# ddk-final-1.net
KiCad netlist of a schematic drawn in EAGLE
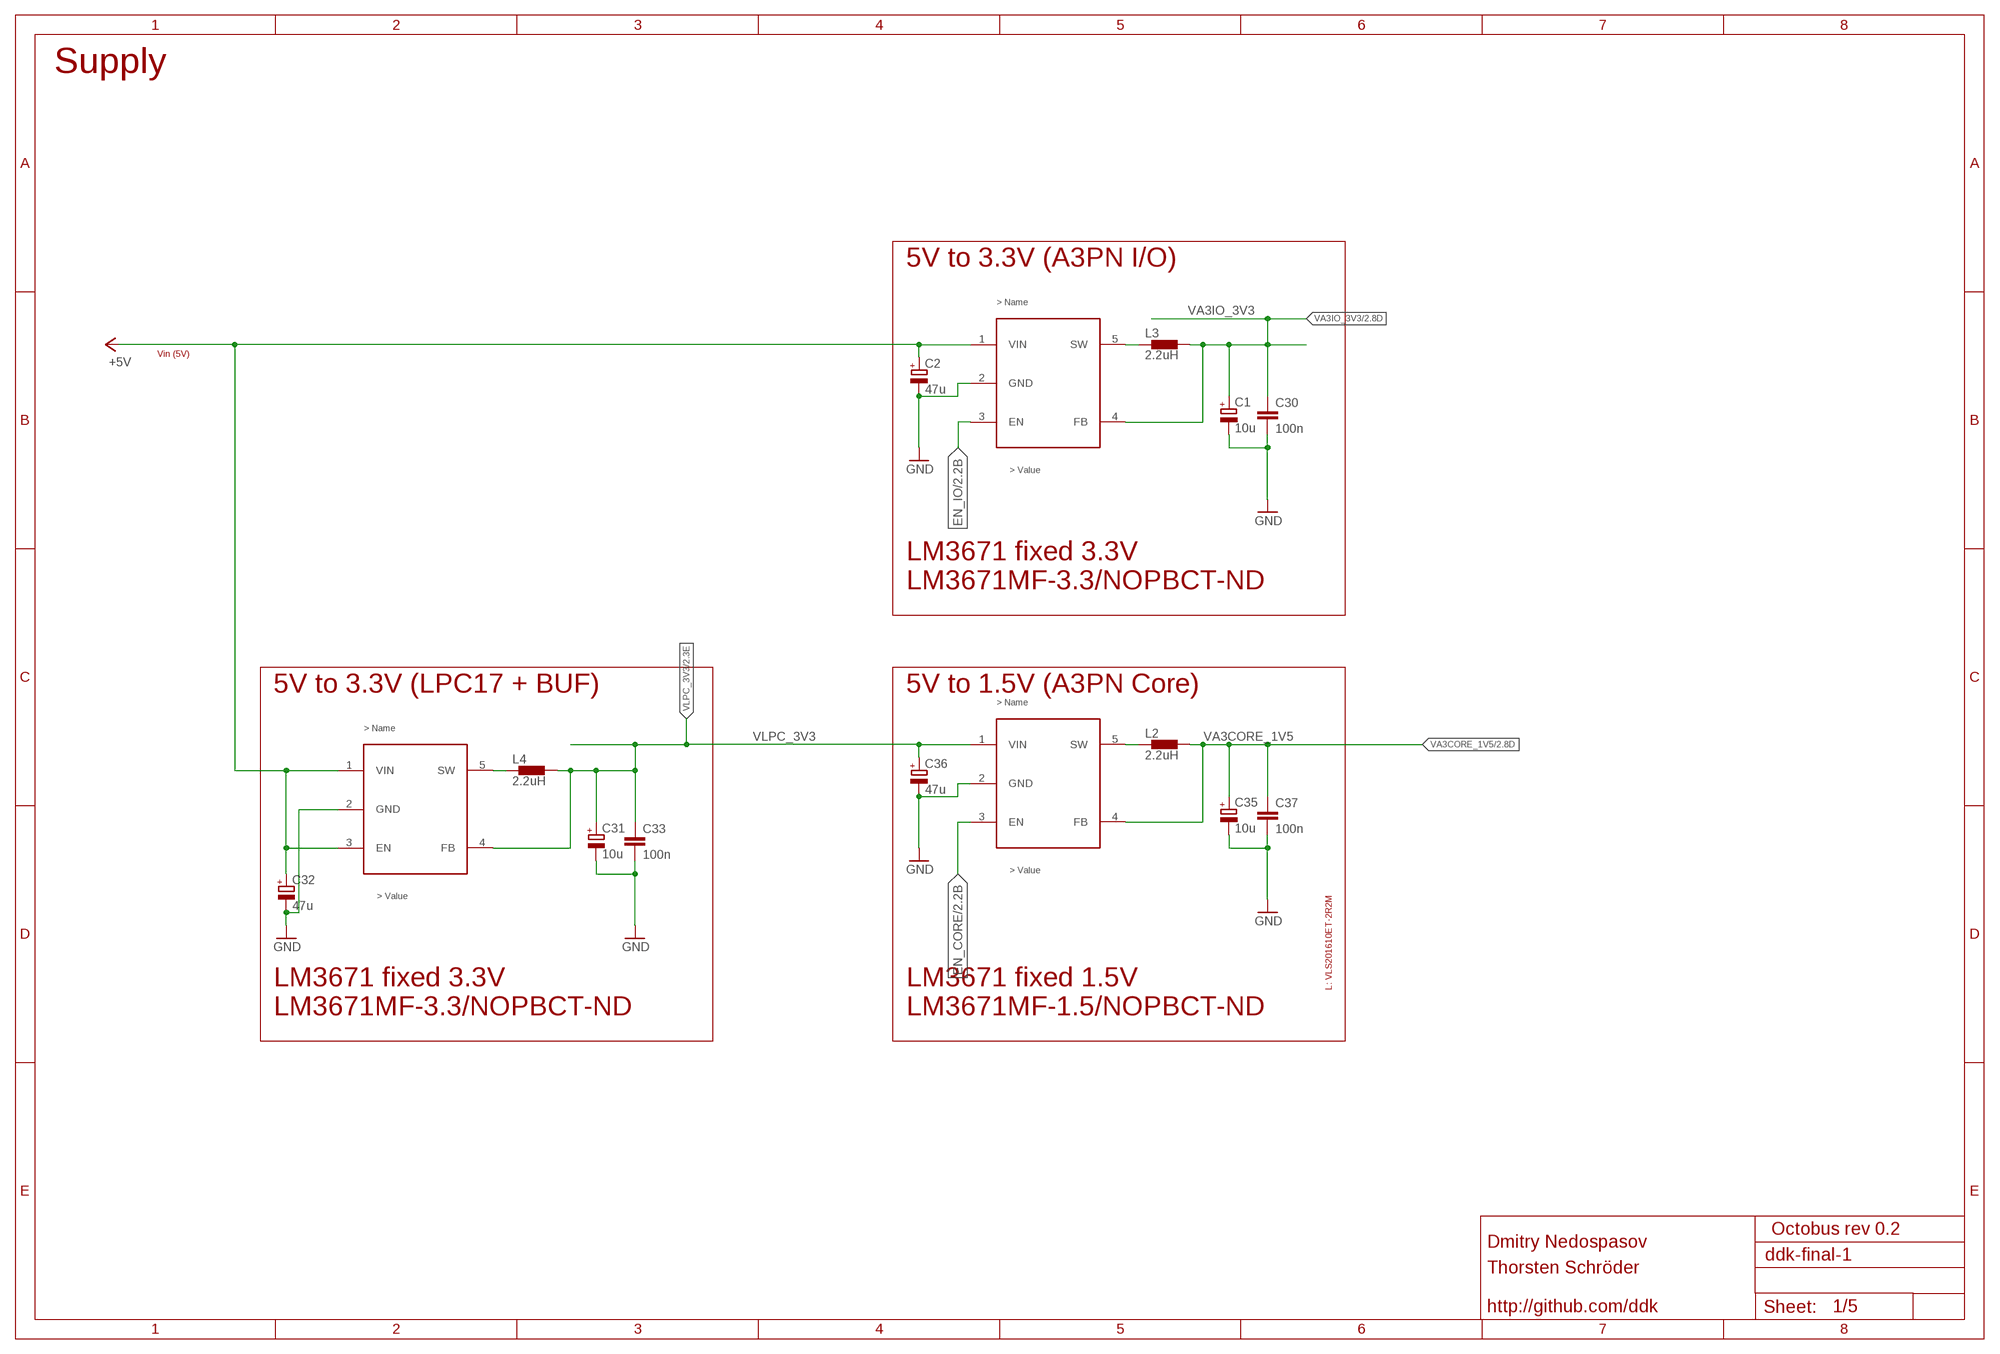
[diagram p0: schematic, sheet 1]
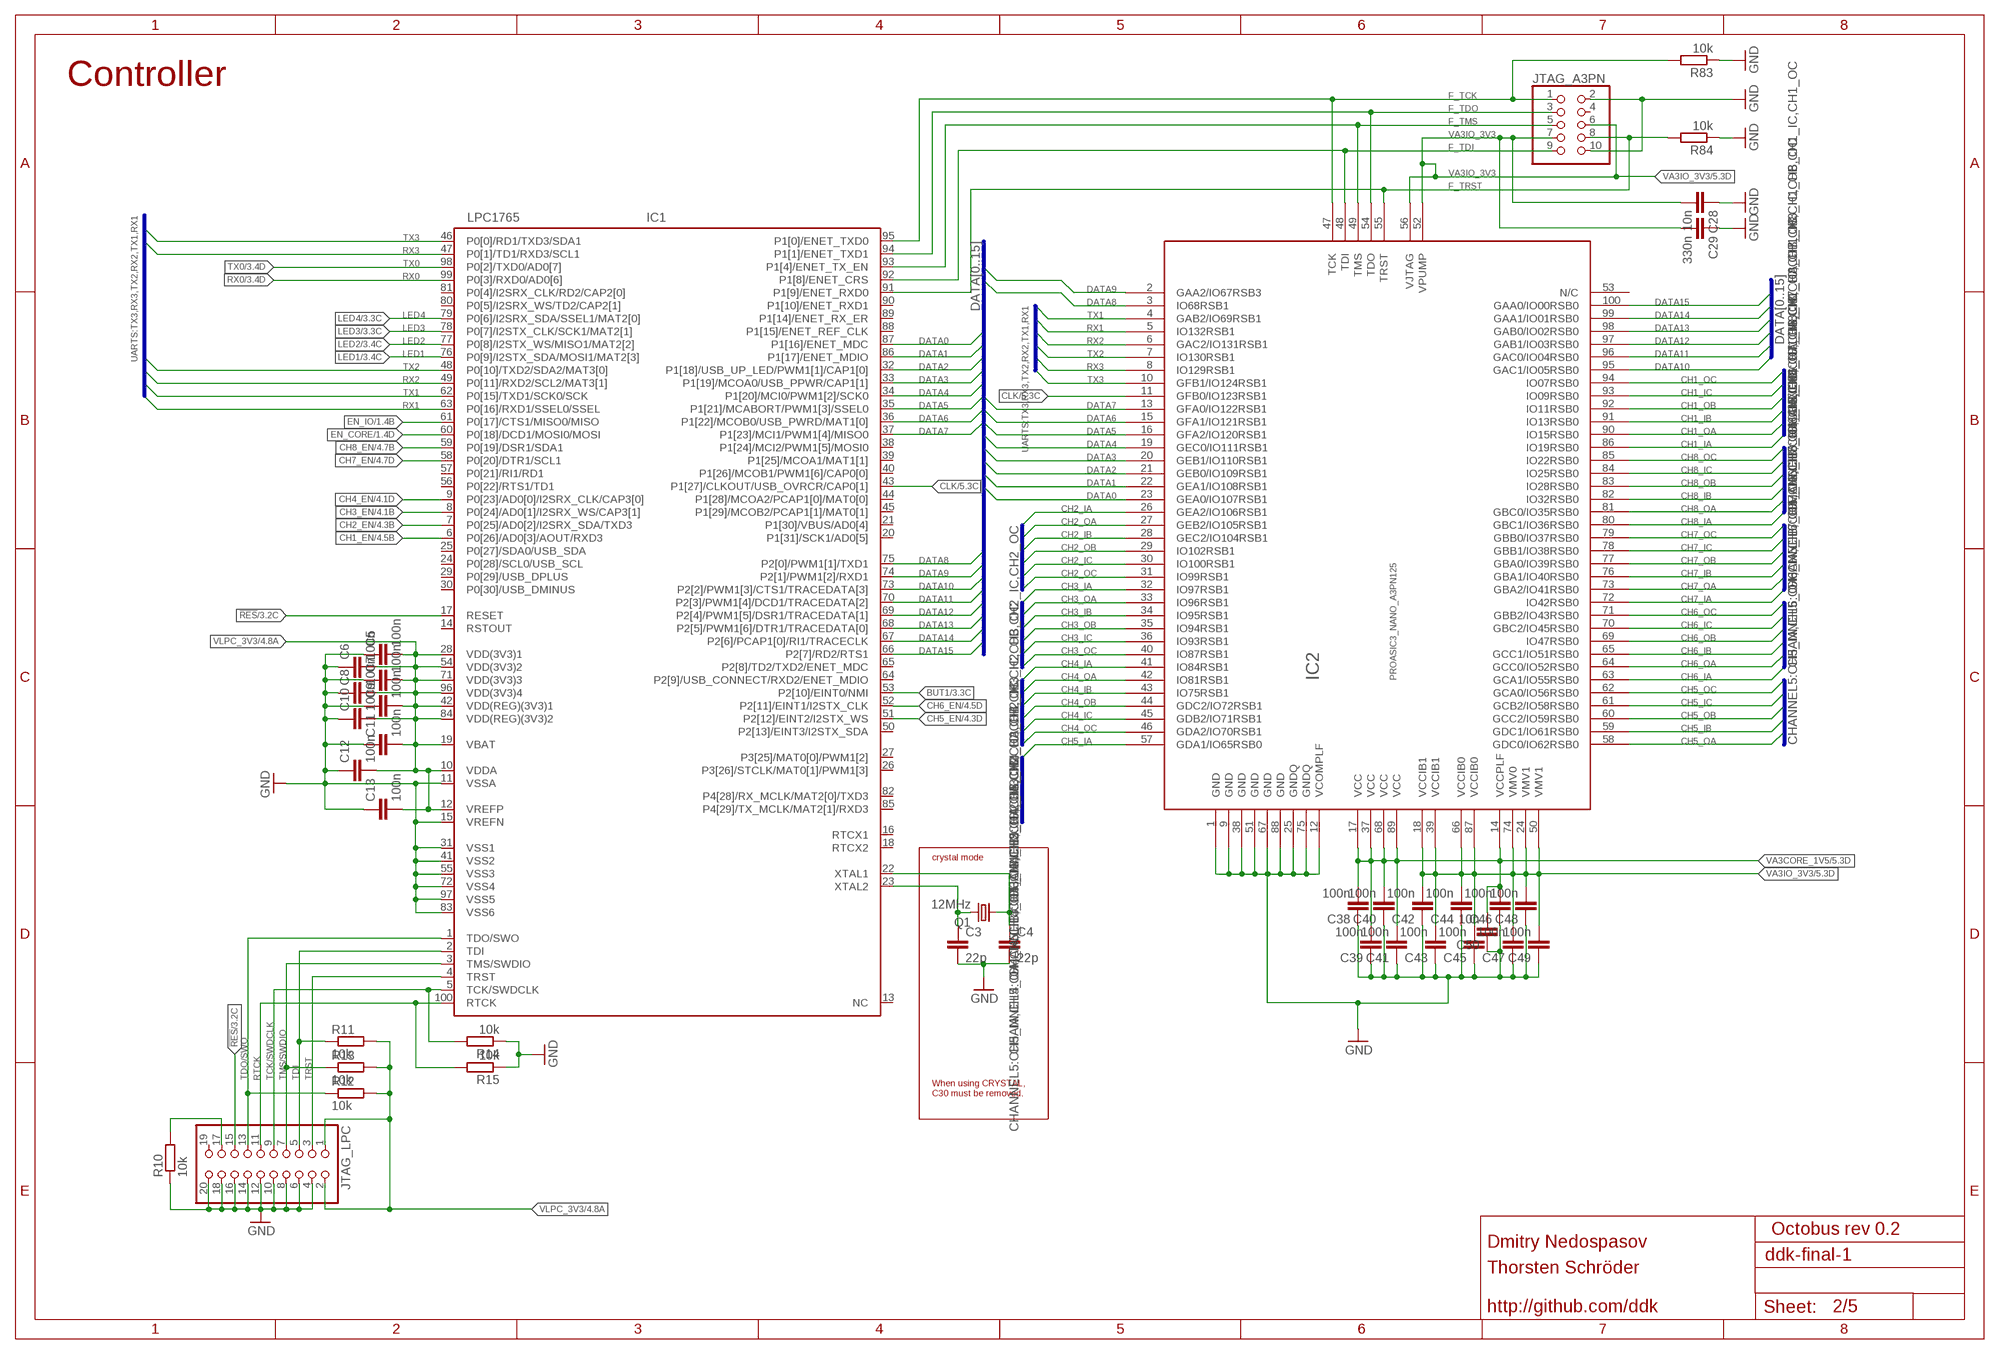
[diagram p1: schematic, sheet 2]
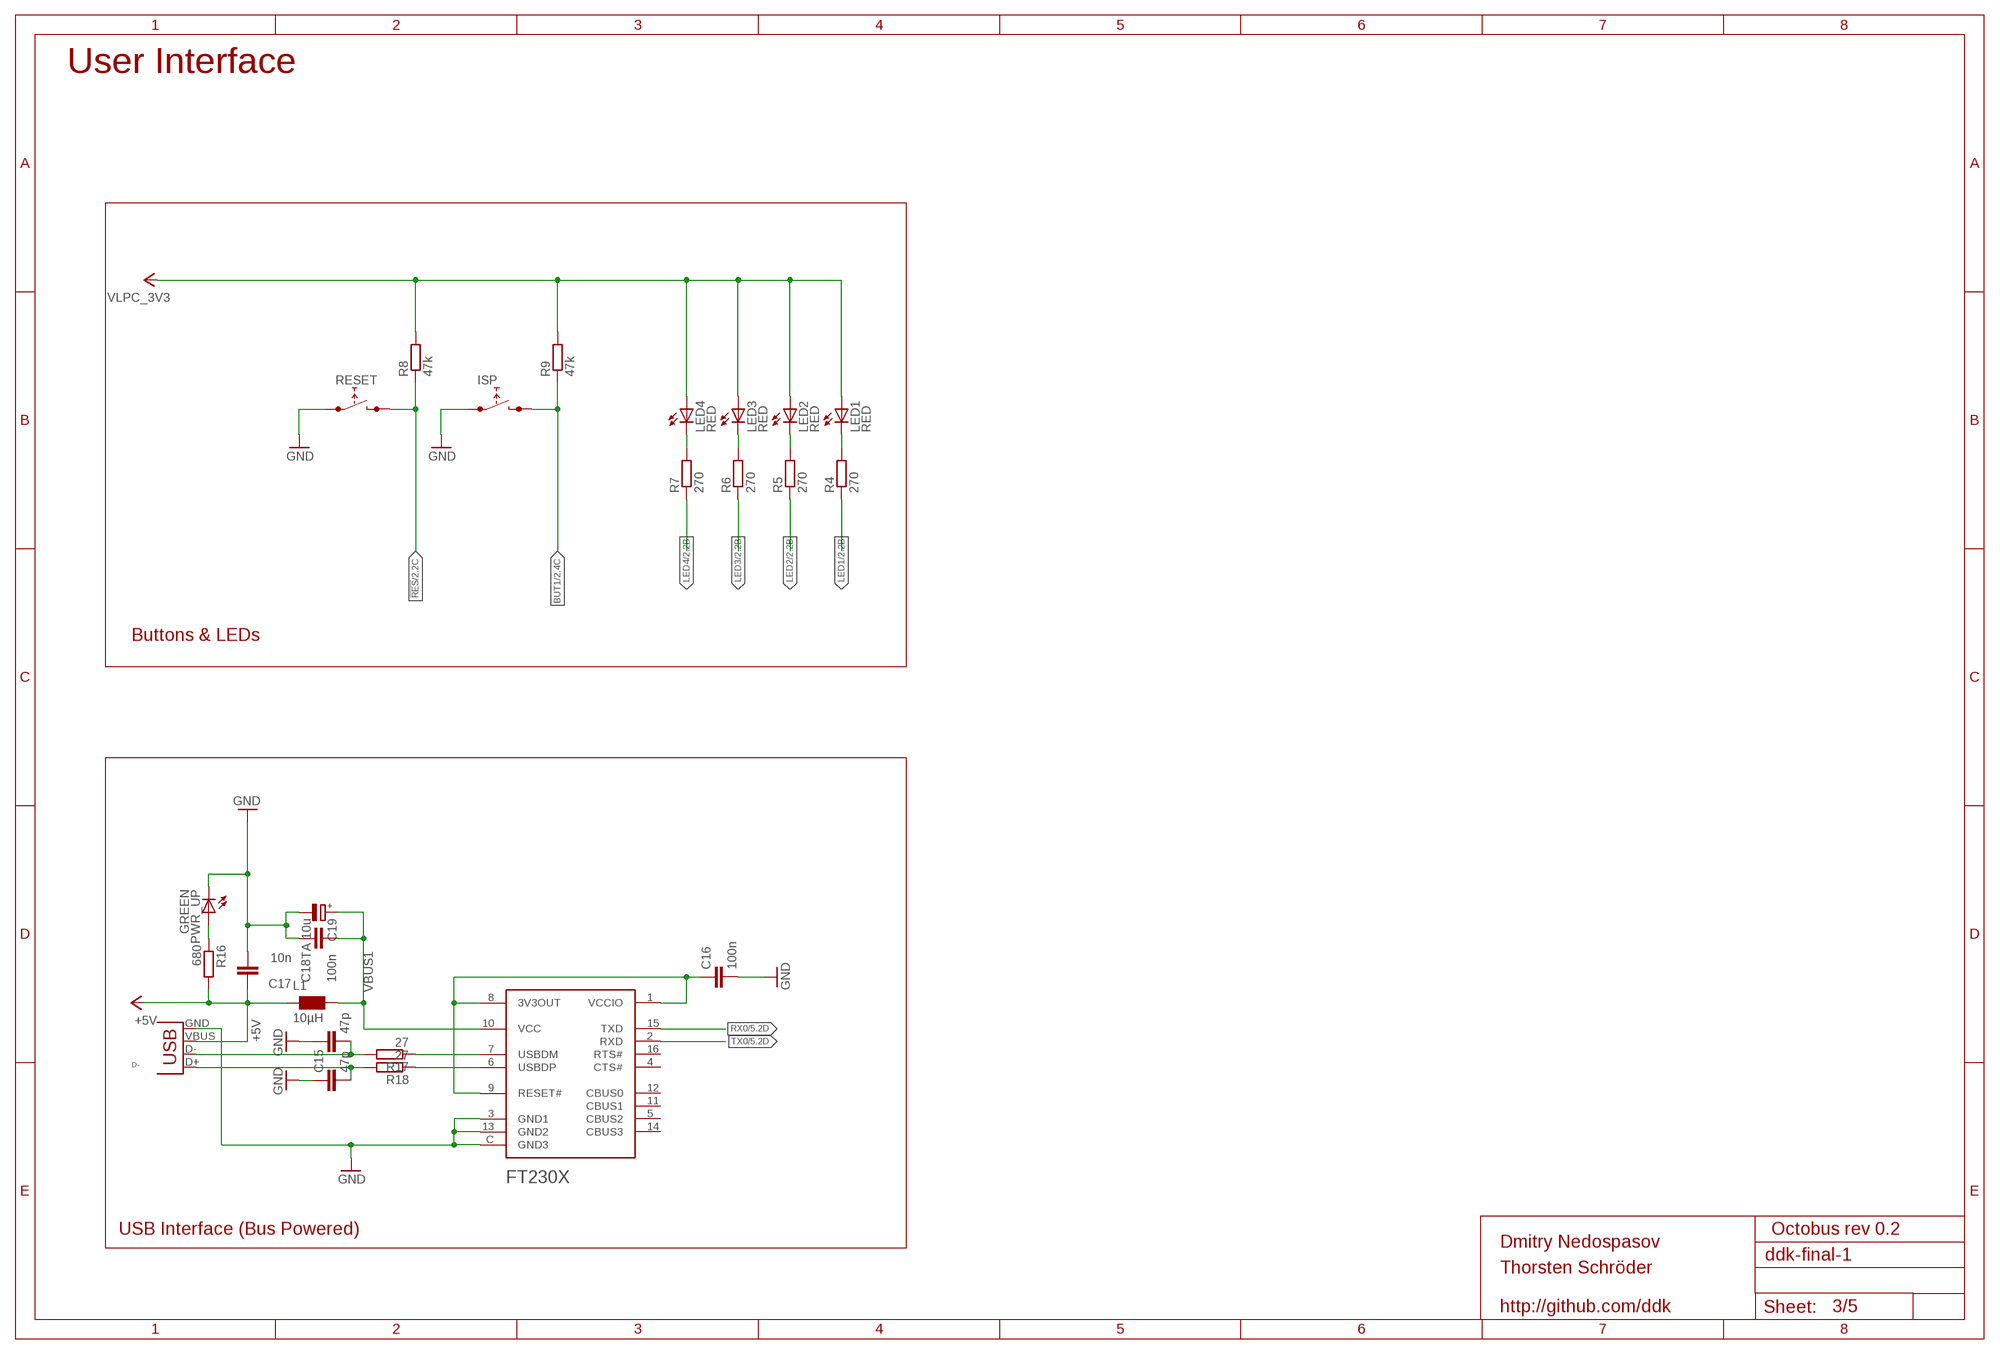
[diagram p2: schematic, sheet 3]
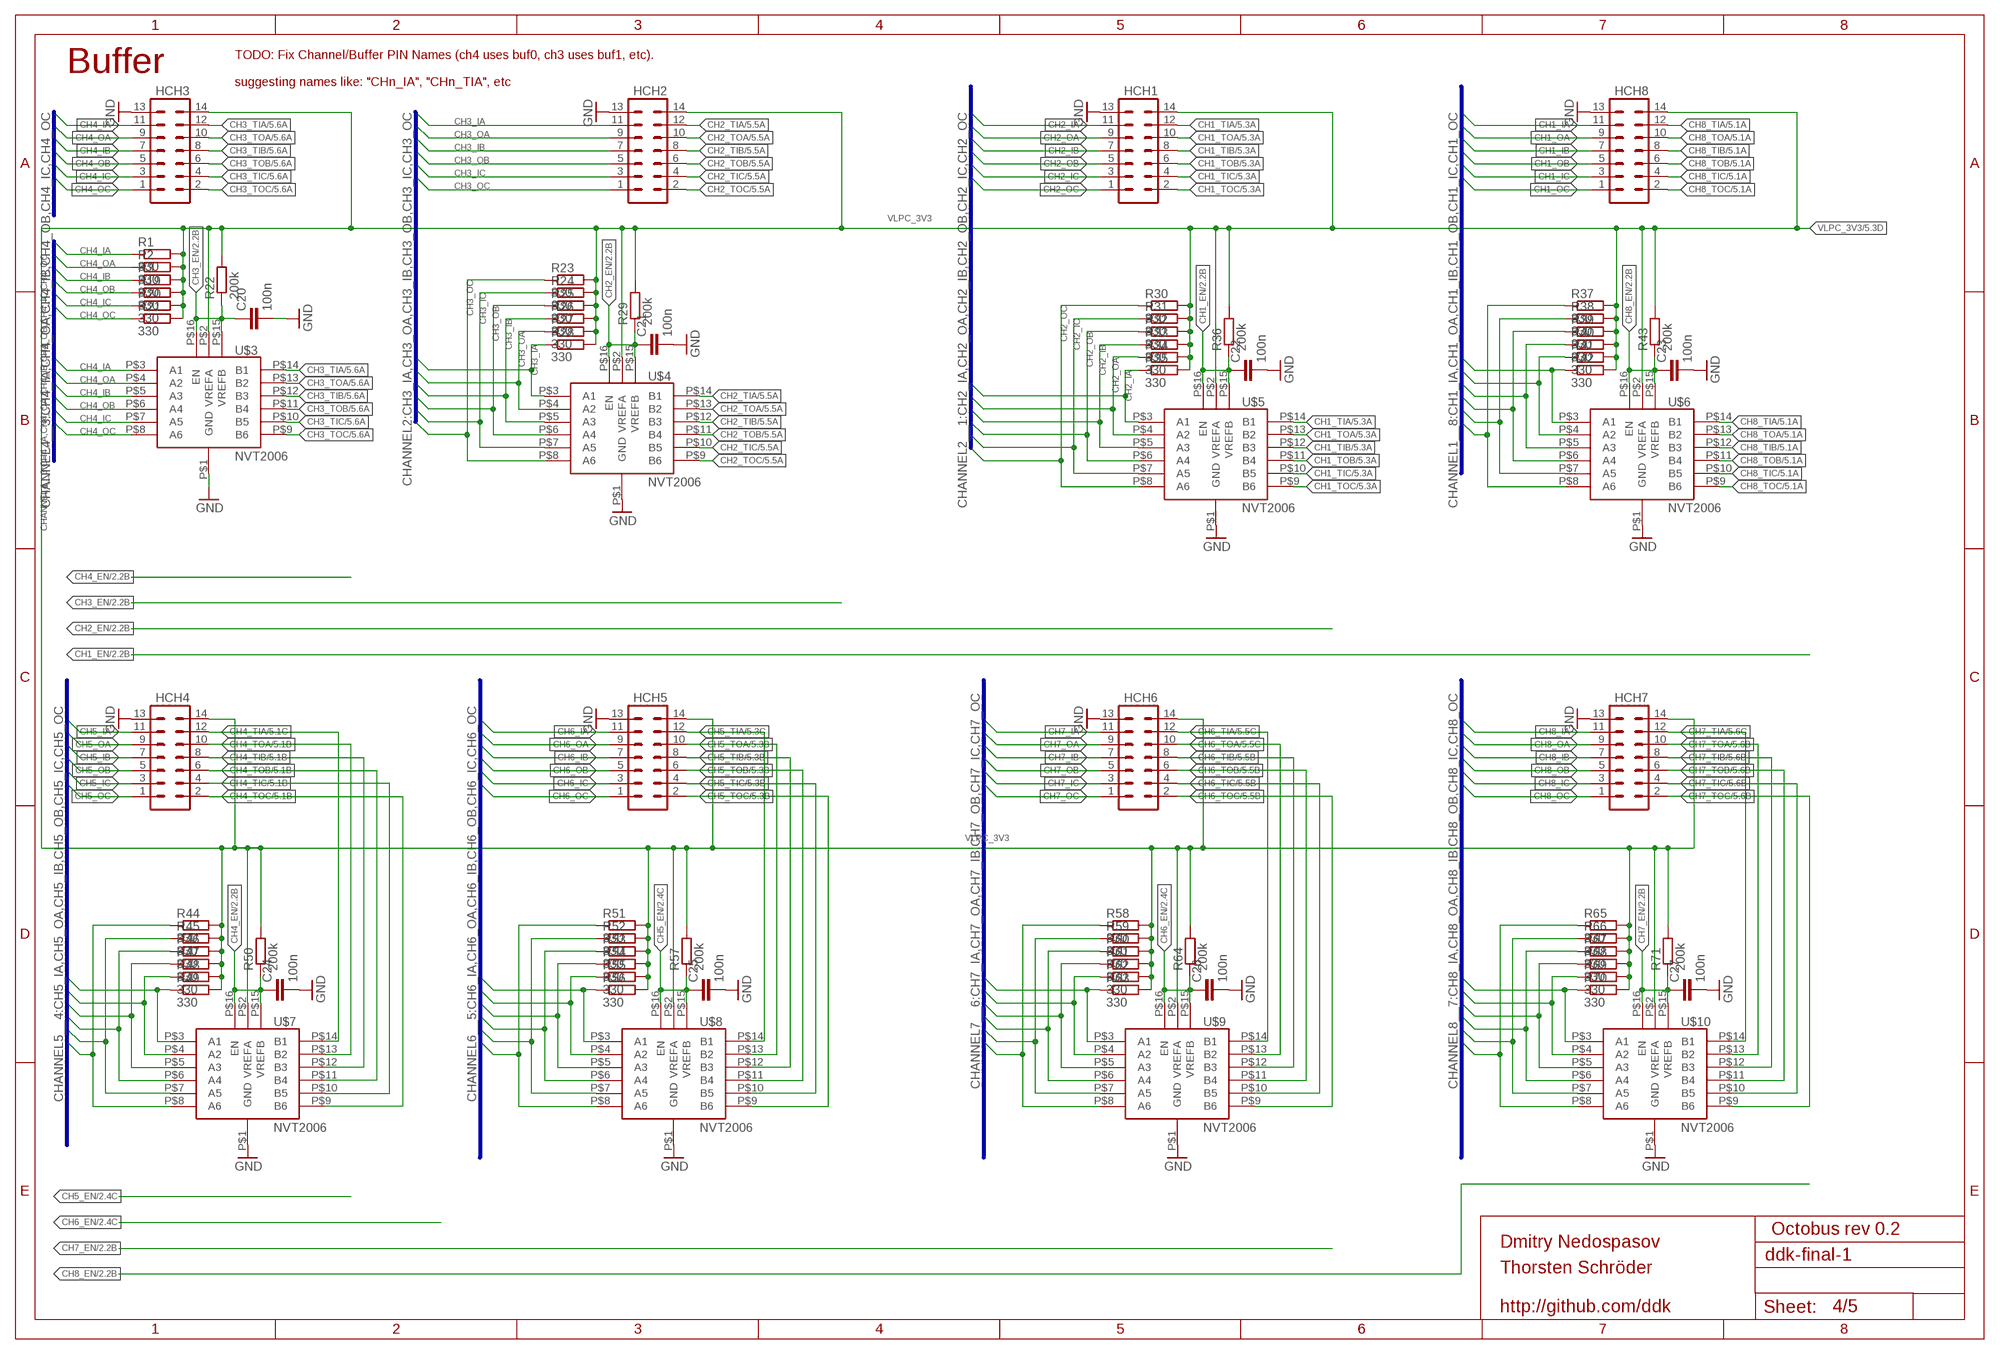
[diagram p3: schematic, sheet 4]
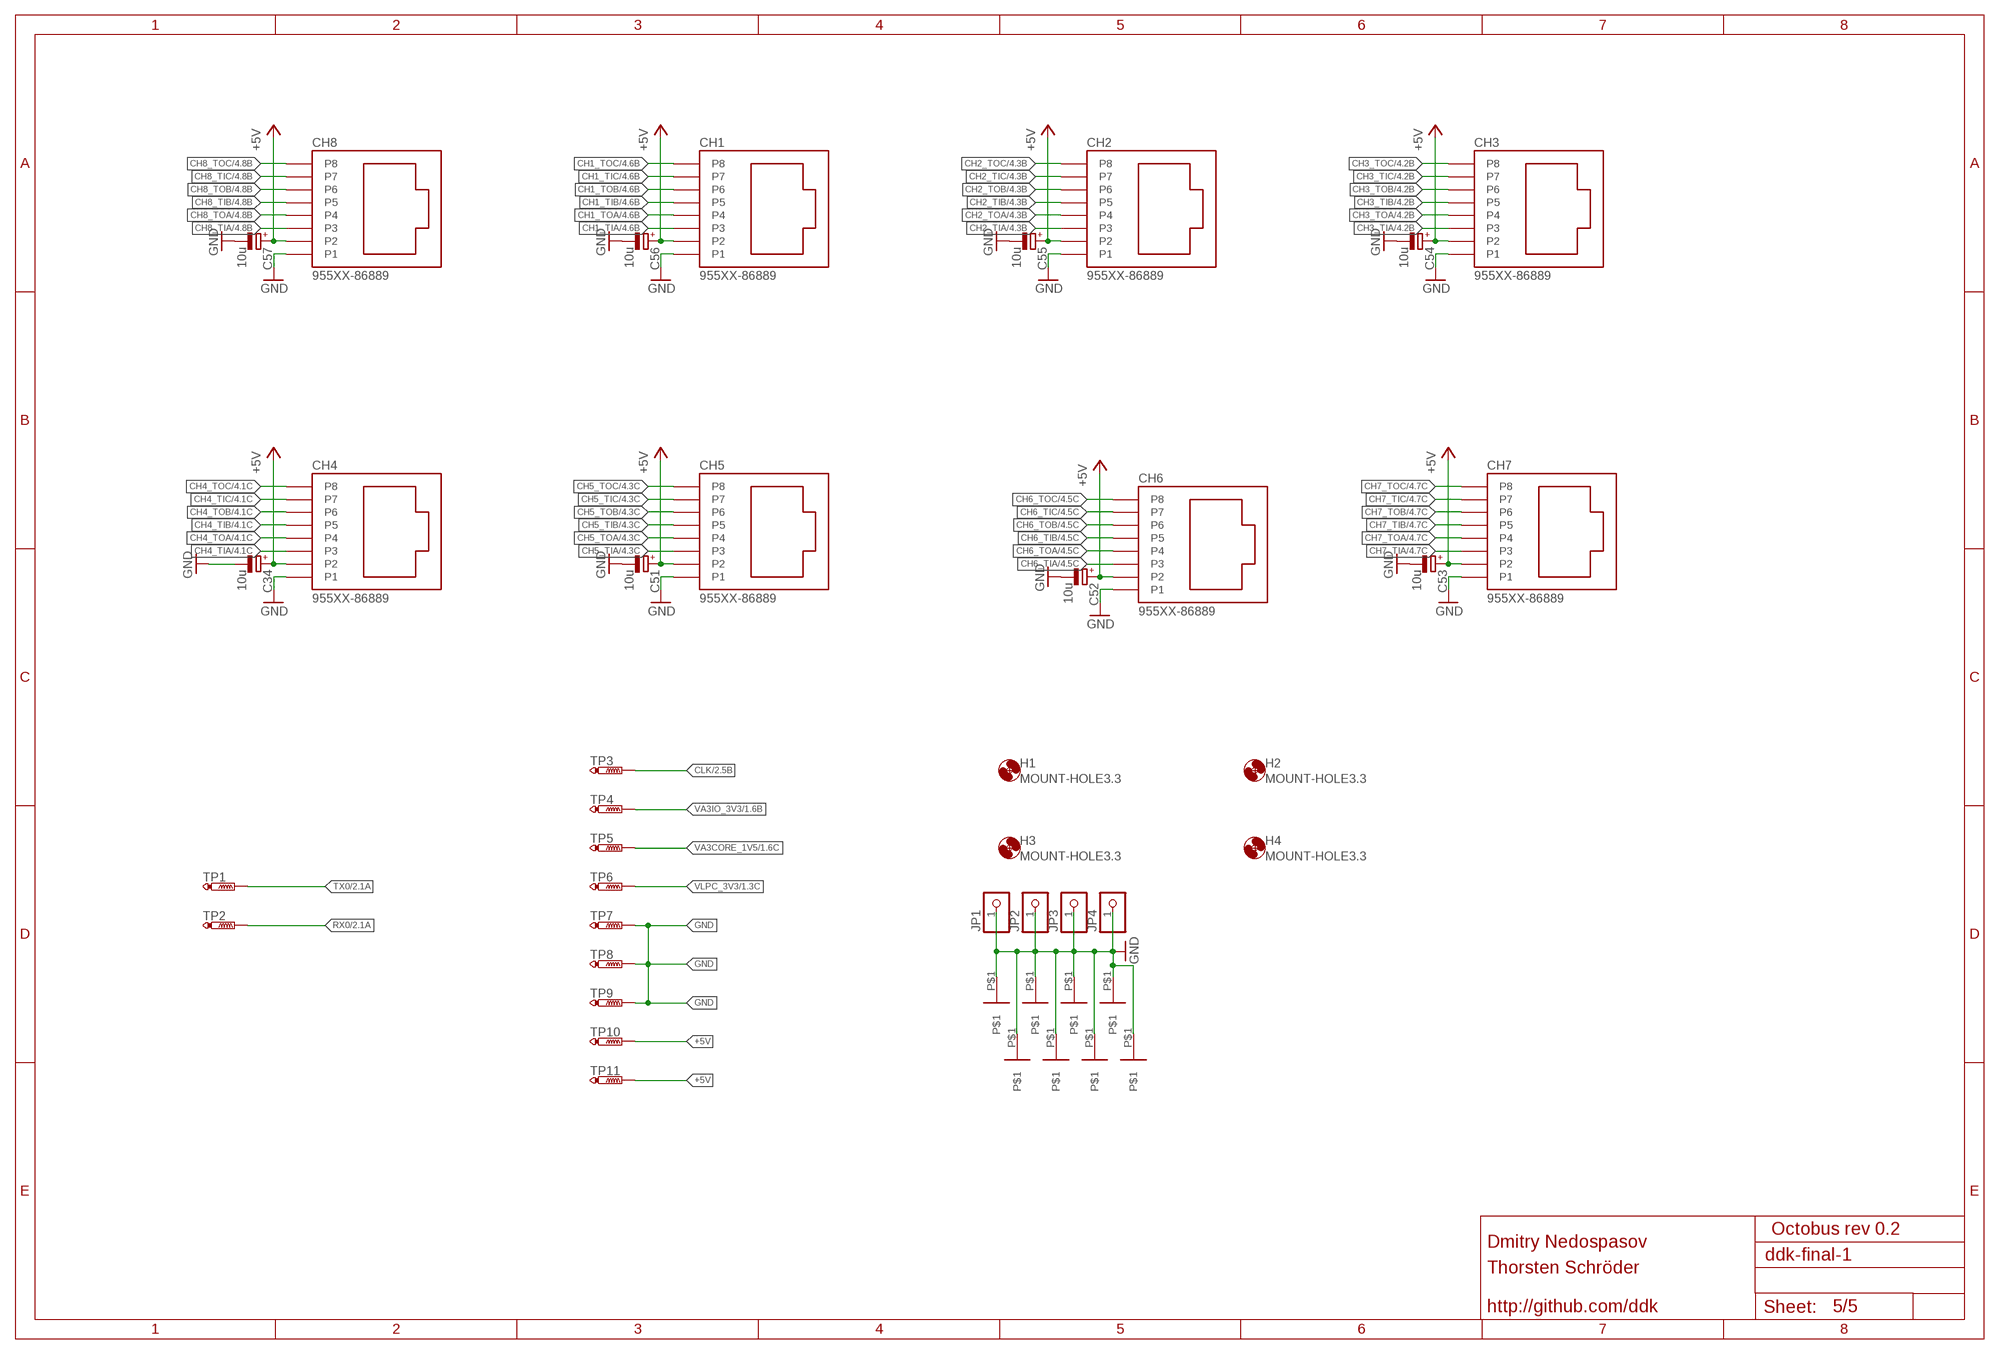
[diagram p4: schematic, sheet 5]

(export (version "E")
  (design (tool "Eeschema 10.0.6"))
  (components
    (comp (ref "C20")
      (value "100n")
      (footprint "eagle-import:C0603")
      (libsource (lib "eagle-import") (part "C-EUC0603"))
    )
    (comp (ref "C21")
      (value "100n")
      (footprint "eagle-import:C0603")
      (libsource (lib "eagle-import") (part "C-EUC0603"))
    )
    (comp (ref "C22")
      (value "100n")
      (footprint "eagle-import:C0603")
      (libsource (lib "eagle-import") (part "C-EUC0603"))
    )
    (comp (ref "C23")
      (value "100n")
      (footprint "eagle-import:C0603")
      (libsource (lib "eagle-import") (part "C-EUC0603"))
    )
    (comp (ref "C24")
      (value "100n")
      (footprint "eagle-import:C0603")
      (libsource (lib "eagle-import") (part "C-EUC0603"))
    )
    (comp (ref "C25")
      (value "100n")
      (footprint "eagle-import:C0603")
      (libsource (lib "eagle-import") (part "C-EUC0603"))
    )
    (comp (ref "C26")
      (value "100n")
      (footprint "eagle-import:C0603")
      (libsource (lib "eagle-import") (part "C-EUC0603"))
    )
    (comp (ref "C27")
      (value "100n")
      (footprint "eagle-import:C0603")
      (libsource (lib "eagle-import") (part "C-EUC0603"))
    )
    (comp (ref "HCH1")
      (value "MA07-2")
      (footprint "eagle-import:MA07-2")
      (libsource (lib "eagle-import") (part "MA07-2"))
    )
    (comp (ref "HCH2")
      (value "MA07-2")
      (footprint "eagle-import:MA07-2")
      (libsource (lib "eagle-import") (part "MA07-2"))
    )
    (comp (ref "HCH3")
      (value "MA07-2")
      (footprint "eagle-import:MA07-2")
      (libsource (lib "eagle-import") (part "MA07-2"))
    )
    (comp (ref "HCH4")
      (value "MA07-2")
      (footprint "eagle-import:MA07-2")
      (libsource (lib "eagle-import") (part "MA07-2"))
    )
    (comp (ref "HCH5")
      (value "MA07-2")
      (footprint "eagle-import:MA07-2")
      (libsource (lib "eagle-import") (part "MA07-2"))
    )
    (comp (ref "HCH6")
      (value "MA07-2")
      (footprint "eagle-import:MA07-2")
      (libsource (lib "eagle-import") (part "MA07-2"))
    )
    (comp (ref "HCH7")
      (value "MA07-2")
      (footprint "eagle-import:MA07-2")
      (libsource (lib "eagle-import") (part "MA07-2"))
    )
    (comp (ref "HCH8")
      (value "MA07-2")
      (footprint "eagle-import:MA07-2")
      (libsource (lib "eagle-import") (part "MA07-2"))
    )
    (comp (ref "R1")
      (value "330")
      (footprint "eagle-import:R0603")
      (libsource (lib "eagle-import") (part "R-EU_R0603"))
    )
    (comp (ref "R2")
      (value "330")
      (footprint "eagle-import:R0603")
      (libsource (lib "eagle-import") (part "R-EU_R0603"))
    )
    (comp (ref "R3")
      (value "330")
      (footprint "eagle-import:R0603")
      (libsource (lib "eagle-import") (part "R-EU_R0603"))
    )
    (comp (ref "R19")
      (value "330")
      (footprint "eagle-import:R0603")
      (libsource (lib "eagle-import") (part "R-EU_R0603"))
    )
    (comp (ref "R20")
      (value "330")
      (footprint "eagle-import:R0603")
      (libsource (lib "eagle-import") (part "R-EU_R0603"))
    )
    (comp (ref "R21")
      (value "330")
      (footprint "eagle-import:R0603")
      (libsource (lib "eagle-import") (part "R-EU_R0603"))
    )
    (comp (ref "R22")
      (value "200k")
      (footprint "eagle-import:R0603")
      (libsource (lib "eagle-import") (part "R-EU_R0603"))
    )
    (comp (ref "R23")
      (value "330")
      (footprint "eagle-import:R0603")
      (libsource (lib "eagle-import") (part "R-EU_R0603"))
    )
    (comp (ref "R24")
      (value "330")
      (footprint "eagle-import:R0603")
      (libsource (lib "eagle-import") (part "R-EU_R0603"))
    )
    (comp (ref "R25")
      (value "330")
      (footprint "eagle-import:R0603")
      (libsource (lib "eagle-import") (part "R-EU_R0603"))
    )
    (comp (ref "R26")
      (value "330")
      (footprint "eagle-import:R0603")
      (libsource (lib "eagle-import") (part "R-EU_R0603"))
    )
    (comp (ref "R27")
      (value "330")
      (footprint "eagle-import:R0603")
      (libsource (lib "eagle-import") (part "R-EU_R0603"))
    )
    (comp (ref "R28")
      (value "330")
      (footprint "eagle-import:R0603")
      (libsource (lib "eagle-import") (part "R-EU_R0603"))
    )
    (comp (ref "R29")
      (value "200k")
      (footprint "eagle-import:R0603")
      (libsource (lib "eagle-import") (part "R-EU_R0603"))
    )
    (comp (ref "R30")
      (value "330")
      (footprint "eagle-import:R0603")
      (libsource (lib "eagle-import") (part "R-EU_R0603"))
    )
    (comp (ref "R31")
      (value "330")
      (footprint "eagle-import:R0603")
      (libsource (lib "eagle-import") (part "R-EU_R0603"))
    )
    (comp (ref "R32")
      (value "330")
      (footprint "eagle-import:R0603")
      (libsource (lib "eagle-import") (part "R-EU_R0603"))
    )
    (comp (ref "R33")
      (value "330")
      (footprint "eagle-import:R0603")
      (libsource (lib "eagle-import") (part "R-EU_R0603"))
    )
    (comp (ref "R34")
      (value "330")
      (footprint "eagle-import:R0603")
      (libsource (lib "eagle-import") (part "R-EU_R0603"))
    )
    (comp (ref "R35")
      (value "330")
      (footprint "eagle-import:R0603")
      (libsource (lib "eagle-import") (part "R-EU_R0603"))
    )
    (comp (ref "R36")
      (value "200k")
      (footprint "eagle-import:R0603")
      (libsource (lib "eagle-import") (part "R-EU_R0603"))
    )
    (comp (ref "R37")
      (value "330")
      (footprint "eagle-import:R0603")
      (libsource (lib "eagle-import") (part "R-EU_R0603"))
    )
    (comp (ref "R38")
      (value "330")
      (footprint "eagle-import:R0603")
      (libsource (lib "eagle-import") (part "R-EU_R0603"))
    )
    (comp (ref "R39")
      (value "330")
      (footprint "eagle-import:R0603")
      (libsource (lib "eagle-import") (part "R-EU_R0603"))
    )
    (comp (ref "R40")
      (value "330")
      (footprint "eagle-import:R0603")
      (libsource (lib "eagle-import") (part "R-EU_R0603"))
    )
    (comp (ref "R41")
      (value "330")
      (footprint "eagle-import:R0603")
      (libsource (lib "eagle-import") (part "R-EU_R0603"))
    )
    (comp (ref "R42")
      (value "330")
      (footprint "eagle-import:R0603")
      (libsource (lib "eagle-import") (part "R-EU_R0603"))
    )
    (comp (ref "R43")
      (value "200k")
      (footprint "eagle-import:R0603")
      (libsource (lib "eagle-import") (part "R-EU_R0603"))
    )
    (comp (ref "R44")
      (value "330")
      (footprint "eagle-import:R0603")
      (libsource (lib "eagle-import") (part "R-EU_R0603"))
    )
    (comp (ref "R45")
      (value "330")
      (footprint "eagle-import:R0603")
      (libsource (lib "eagle-import") (part "R-EU_R0603"))
    )
    (comp (ref "R46")
      (value "330")
      (footprint "eagle-import:R0603")
      (libsource (lib "eagle-import") (part "R-EU_R0603"))
    )
    (comp (ref "R47")
      (value "330")
      (footprint "eagle-import:R0603")
      (libsource (lib "eagle-import") (part "R-EU_R0603"))
    )
    (comp (ref "R48")
      (value "330")
      (footprint "eagle-import:R0603")
      (libsource (lib "eagle-import") (part "R-EU_R0603"))
    )
    (comp (ref "R49")
      (value "330")
      (footprint "eagle-import:R0603")
      (libsource (lib "eagle-import") (part "R-EU_R0603"))
    )
    (comp (ref "R50")
      (value "200k")
      (footprint "eagle-import:R0603")
      (libsource (lib "eagle-import") (part "R-EU_R0603"))
    )
    (comp (ref "R51")
      (value "330")
      (footprint "eagle-import:R0603")
      (libsource (lib "eagle-import") (part "R-EU_R0603"))
    )
    (comp (ref "R52")
      (value "330")
      (footprint "eagle-import:R0603")
      (libsource (lib "eagle-import") (part "R-EU_R0603"))
    )
    (comp (ref "R53")
      (value "330")
      (footprint "eagle-import:R0603")
      (libsource (lib "eagle-import") (part "R-EU_R0603"))
    )
    (comp (ref "R54")
      (value "330")
      (footprint "eagle-import:R0603")
      (libsource (lib "eagle-import") (part "R-EU_R0603"))
    )
    (comp (ref "R55")
      (value "330")
      (footprint "eagle-import:R0603")
      (libsource (lib "eagle-import") (part "R-EU_R0603"))
    )
    (comp (ref "R56")
      (value "330")
      (footprint "eagle-import:R0603")
      (libsource (lib "eagle-import") (part "R-EU_R0603"))
    )
    (comp (ref "R57")
      (value "200k")
      (footprint "eagle-import:R0603")
      (libsource (lib "eagle-import") (part "R-EU_R0603"))
    )
    (comp (ref "R58")
      (value "330")
      (footprint "eagle-import:R0603")
      (libsource (lib "eagle-import") (part "R-EU_R0603"))
    )
    (comp (ref "R59")
      (value "330")
      (footprint "eagle-import:R0603")
      (libsource (lib "eagle-import") (part "R-EU_R0603"))
    )
    (comp (ref "R60")
      (value "330")
      (footprint "eagle-import:R0603")
      (libsource (lib "eagle-import") (part "R-EU_R0603"))
    )
    (comp (ref "R61")
      (value "330")
      (footprint "eagle-import:R0603")
      (libsource (lib "eagle-import") (part "R-EU_R0603"))
    )
    (comp (ref "R62")
      (value "330")
      (footprint "eagle-import:R0603")
      (libsource (lib "eagle-import") (part "R-EU_R0603"))
    )
    (comp (ref "R63")
      (value "330")
      (footprint "eagle-import:R0603")
      (libsource (lib "eagle-import") (part "R-EU_R0603"))
    )
    (comp (ref "R64")
      (value "200k")
      (footprint "eagle-import:R0603")
      (libsource (lib "eagle-import") (part "R-EU_R0603"))
    )
    (comp (ref "R65")
      (value "330")
      (footprint "eagle-import:R0603")
      (libsource (lib "eagle-import") (part "R-EU_R0603"))
    )
    (comp (ref "R66")
      (value "330")
      (footprint "eagle-import:R0603")
      (libsource (lib "eagle-import") (part "R-EU_R0603"))
    )
    (comp (ref "R67")
      (value "330")
      (footprint "eagle-import:R0603")
      (libsource (lib "eagle-import") (part "R-EU_R0603"))
    )
    (comp (ref "R68")
      (value "330")
      (footprint "eagle-import:R0603")
      (libsource (lib "eagle-import") (part "R-EU_R0603"))
    )
    (comp (ref "R69")
      (value "330")
      (footprint "eagle-import:R0603")
      (libsource (lib "eagle-import") (part "R-EU_R0603"))
    )
    (comp (ref "R70")
      (value "330")
      (footprint "eagle-import:R0603")
      (libsource (lib "eagle-import") (part "R-EU_R0603"))
    )
    (comp (ref "R71")
      (value "200k")
      (footprint "eagle-import:R0603")
      (libsource (lib "eagle-import") (part "R-EU_R0603"))
    )
    (comp (ref "U$3")
      (value "NVT2006")
      (footprint "eagle-import:TSSOP16")
      (libsource (lib "eagle-import") (part "NVT2006"))
    )
    (comp (ref "U$4")
      (value "NVT2006")
      (footprint "eagle-import:TSSOP16")
      (libsource (lib "eagle-import") (part "NVT2006"))
    )
    (comp (ref "U$5")
      (value "NVT2006")
      (footprint "eagle-import:TSSOP16")
      (libsource (lib "eagle-import") (part "NVT2006"))
    )
    (comp (ref "U$6")
      (value "NVT2006")
      (footprint "eagle-import:TSSOP16")
      (libsource (lib "eagle-import") (part "NVT2006"))
    )
    (comp (ref "U$7")
      (value "NVT2006")
      (footprint "eagle-import:TSSOP16")
      (libsource (lib "eagle-import") (part "NVT2006"))
    )
    (comp (ref "U$8")
      (value "NVT2006")
      (footprint "eagle-import:TSSOP16")
      (libsource (lib "eagle-import") (part "NVT2006"))
    )
    (comp (ref "U$9")
      (value "NVT2006")
      (footprint "eagle-import:TSSOP16")
      (libsource (lib "eagle-import") (part "NVT2006"))
    )
    (comp (ref "U$10")
      (value "NVT2006")
      (footprint "eagle-import:TSSOP16")
      (libsource (lib "eagle-import") (part "NVT2006"))
    )
    (comp (ref "C34")
      (value "10u")
      (footprint "eagle-import:CT3216")
      (libsource (lib "eagle-import") (part "CPOL-EUCT3216"))
    )
    (comp (ref "C51")
      (value "10u")
      (footprint "eagle-import:CT3216")
      (libsource (lib "eagle-import") (part "CPOL-EUCT3216"))
    )
    (comp (ref "C52")
      (value "10u")
      (footprint "eagle-import:CT3216")
      (libsource (lib "eagle-import") (part "CPOL-EUCT3216"))
    )
    (comp (ref "C53")
      (value "10u")
      (footprint "eagle-import:CT3216")
      (libsource (lib "eagle-import") (part "CPOL-EUCT3216"))
    )
    (comp (ref "C54")
      (value "10u")
      (footprint "eagle-import:CT3216")
      (libsource (lib "eagle-import") (part "CPOL-EUCT3216"))
    )
    (comp (ref "C55")
      (value "10u")
      (footprint "eagle-import:CT3216")
      (libsource (lib "eagle-import") (part "CPOL-EUCT3216"))
    )
    (comp (ref "C56")
      (value "10u")
      (footprint "eagle-import:CT3216")
      (libsource (lib "eagle-import") (part "CPOL-EUCT3216"))
    )
    (comp (ref "C57")
      (value "10u")
      (footprint "eagle-import:CT3216")
      (libsource (lib "eagle-import") (part "CPOL-EUCT3216"))
    )
    (comp (ref "CH1")
      (value "955XX-86889")
      (footprint "eagle-import:95501")
      (libsource (lib "eagle-import") (part "955XX-86889"))
    )
    (comp (ref "CH2")
      (value "955XX-86889")
      (footprint "eagle-import:95501")
      (libsource (lib "eagle-import") (part "955XX-86889"))
    )
    (comp (ref "CH3")
      (value "955XX-86889")
      (footprint "eagle-import:95501")
      (libsource (lib "eagle-import") (part "955XX-86889"))
    )
    (comp (ref "CH4")
      (value "955XX-86889")
      (footprint "eagle-import:95501")
      (libsource (lib "eagle-import") (part "955XX-86889"))
    )
    (comp (ref "CH5")
      (value "955XX-86889")
      (footprint "eagle-import:95501")
      (libsource (lib "eagle-import") (part "955XX-86889"))
    )
    (comp (ref "CH6")
      (value "955XX-86889")
      (footprint "eagle-import:95501")
      (libsource (lib "eagle-import") (part "955XX-86889"))
    )
    (comp (ref "CH7")
      (value "955XX-86889")
      (footprint "eagle-import:95501")
      (libsource (lib "eagle-import") (part "955XX-86889"))
    )
    (comp (ref "CH8")
      (value "955XX-86889")
      (footprint "eagle-import:95501")
      (libsource (lib "eagle-import") (part "955XX-86889"))
    )
    (comp (ref "H1")
      (value "MOUNT-HOLE3.3")
      (footprint "eagle-import:3,3")
      (libsource (lib "eagle-import") (part "MOUNT-HOLE3.3"))
    )
    (comp (ref "H2")
      (value "MOUNT-HOLE3.3")
      (footprint "eagle-import:3,3")
      (libsource (lib "eagle-import") (part "MOUNT-HOLE3.3"))
    )
    (comp (ref "H3")
      (value "MOUNT-HOLE3.3")
      (footprint "eagle-import:3,3")
      (libsource (lib "eagle-import") (part "MOUNT-HOLE3.3"))
    )
    (comp (ref "H4")
      (value "MOUNT-HOLE3.3")
      (footprint "eagle-import:3,3")
      (libsource (lib "eagle-import") (part "MOUNT-HOLE3.3"))
    )
    (comp (ref "JP1")
      (value "PINHD-1X1")
      (footprint "eagle-import:1X01")
      (libsource (lib "eagle-import") (part "PINHD-1X1"))
    )
    (comp (ref "JP2")
      (value "PINHD-1X1")
      (footprint "eagle-import:1X01")
      (libsource (lib "eagle-import") (part "PINHD-1X1"))
    )
    (comp (ref "JP3")
      (value "PINHD-1X1")
      (footprint "eagle-import:1X01")
      (libsource (lib "eagle-import") (part "PINHD-1X1"))
    )
    (comp (ref "JP4")
      (value "PINHD-1X1")
      (footprint "eagle-import:1X01")
      (libsource (lib "eagle-import") (part "PINHD-1X1"))
    )
    (comp (ref "TP1")
      (value "PTR1B1,27")
      (footprint "eagle-import:B1,27")
      (libsource (lib "eagle-import") (part "PTR1B1,27"))
    )
    (comp (ref "TP2")
      (value "PTR1B1,27")
      (footprint "eagle-import:B1,27")
      (libsource (lib "eagle-import") (part "PTR1B1,27"))
    )
    (comp (ref "TP3")
      (value "PTR1TP08R")
      (footprint "eagle-import:TP08R")
      (libsource (lib "eagle-import") (part "PTR1TP08R"))
    )
    (comp (ref "TP4")
      (value "PTR1B1,27")
      (footprint "eagle-import:B1,27")
      (libsource (lib "eagle-import") (part "PTR1B1,27"))
    )
    (comp (ref "TP5")
      (value "PTR1B1,27")
      (footprint "eagle-import:B1,27")
      (libsource (lib "eagle-import") (part "PTR1B1,27"))
    )
    (comp (ref "TP6")
      (value "PTR1B1,27")
      (footprint "eagle-import:B1,27")
      (libsource (lib "eagle-import") (part "PTR1B1,27"))
    )
    (comp (ref "TP7")
      (value "PTR1B1,27")
      (footprint "eagle-import:B1,27")
      (libsource (lib "eagle-import") (part "PTR1B1,27"))
    )
    (comp (ref "TP8")
      (value "PTR1B1,27")
      (footprint "eagle-import:B1,27")
      (libsource (lib "eagle-import") (part "PTR1B1,27"))
    )
    (comp (ref "TP9")
      (value "PTR1B1,27")
      (footprint "eagle-import:B1,27")
      (libsource (lib "eagle-import") (part "PTR1B1,27"))
    )
    (comp (ref "TP10")
      (value "PTR1B1,27")
      (footprint "eagle-import:B1,27")
      (libsource (lib "eagle-import") (part "PTR1B1,27"))
    )
    (comp (ref "TP11")
      (value "PTR1B1,27")
      (footprint "eagle-import:B1,27")
      (libsource (lib "eagle-import") (part "PTR1B1,27"))
    )
    (comp (ref "U$11")
      (value "GNDPAD_4MM")
      (footprint "eagle-import:GNDPAD")
      (libsource (lib "eagle-import") (part "GNDPAD_4MM"))
    )
    (comp (ref "U$12")
      (value "GNDPAD_4MM")
      (footprint "eagle-import:GNDPAD")
      (libsource (lib "eagle-import") (part "GNDPAD_4MM"))
    )
    (comp (ref "U$13")
      (value "GNDPAD_4MM")
      (footprint "eagle-import:GNDPAD")
      (libsource (lib "eagle-import") (part "GNDPAD_4MM"))
    )
    (comp (ref "U$14")
      (value "GNDPAD_4MM")
      (footprint "eagle-import:GNDPAD")
      (libsource (lib "eagle-import") (part "GNDPAD_4MM"))
    )
    (comp (ref "U$15")
      (value "GNDPAD_4MM")
      (footprint "eagle-import:GNDPAD")
      (libsource (lib "eagle-import") (part "GNDPAD_4MM"))
    )
    (comp (ref "U$16")
      (value "GNDPAD_4MM")
      (footprint "eagle-import:GNDPAD")
      (libsource (lib "eagle-import") (part "GNDPAD_4MM"))
    )
    (comp (ref "U$17")
      (value "GNDPAD_4MM")
      (footprint "eagle-import:GNDPAD")
      (libsource (lib "eagle-import") (part "GNDPAD_4MM"))
    )
    (comp (ref "U$18")
      (value "GNDPAD_4MM")
      (footprint "eagle-import:GNDPAD")
      (libsource (lib "eagle-import") (part "GNDPAD_4MM"))
    )
    (comp (ref "C3")
      (value "22p")
      (footprint "eagle-import:C0603K")
      (libsource (lib "eagle-import") (part "C-EUC0603K"))
    )
    (comp (ref "C4")
      (value "22p")
      (footprint "eagle-import:C0603K")
      (libsource (lib "eagle-import") (part "C-EUC0603K"))
    )
    (comp (ref "C5")
      (value "100n")
      (footprint "eagle-import:C0603K")
      (libsource (lib "eagle-import") (part "C-EUC0603K"))
    )
    (comp (ref "C6")
      (value "100n")
      (footprint "eagle-import:C0603K")
      (libsource (lib "eagle-import") (part "C-EUC0603K"))
    )
    (comp (ref "C7")
      (value "100n")
      (footprint "eagle-import:C0603K")
      (libsource (lib "eagle-import") (part "C-EUC0603K"))
    )
    (comp (ref "C8")
      (value "100n")
      (footprint "eagle-import:C0603K")
      (libsource (lib "eagle-import") (part "C-EUC0603K"))
    )
    (comp (ref "C9")
      (value "100n")
      (footprint "eagle-import:C0603K")
      (libsource (lib "eagle-import") (part "C-EUC0603K"))
    )
    (comp (ref "C10")
      (value "100n")
      (footprint "eagle-import:C0603K")
      (libsource (lib "eagle-import") (part "C-EUC0603K"))
    )
    (comp (ref "C11")
      (value "100n")
      (footprint "eagle-import:C0603K")
      (libsource (lib "eagle-import") (part "C-EUC0603K"))
    )
    (comp (ref "C12")
      (value "100n")
      (footprint "eagle-import:C0603K")
      (libsource (lib "eagle-import") (part "C-EUC0603K"))
    )
    (comp (ref "C13")
      (value "100n")
      (footprint "eagle-import:C0603K")
      (libsource (lib "eagle-import") (part "C-EUC0603K"))
    )
    (comp (ref "C28")
      (value "10n")
      (footprint "eagle-import:C0603K")
      (libsource (lib "eagle-import") (part "C-EUC0603K"))
    )
    (comp (ref "C29")
      (value "330n")
      (footprint "eagle-import:C0603K")
      (libsource (lib "eagle-import") (part "C-EUC0603K"))
    )
    (comp (ref "C38")
      (value "100n")
      (footprint "eagle-import:C0603K")
      (libsource (lib "eagle-import") (part "C-EUC0603K"))
    )
    (comp (ref "C39")
      (value "100n")
      (footprint "eagle-import:C0603K")
      (libsource (lib "eagle-import") (part "C-EUC0603K"))
    )
    (comp (ref "C40")
      (value "100n")
      (footprint "eagle-import:C0603K")
      (libsource (lib "eagle-import") (part "C-EUC0603K"))
    )
    (comp (ref "C41")
      (value "100n")
      (footprint "eagle-import:C0603K")
      (libsource (lib "eagle-import") (part "C-EUC0603K"))
    )
    (comp (ref "C42")
      (value "100n")
      (footprint "eagle-import:C0603K")
      (libsource (lib "eagle-import") (part "C-EUC0603K"))
    )
    (comp (ref "C43")
      (value "100n")
      (footprint "eagle-import:C0603K")
      (libsource (lib "eagle-import") (part "C-EUC0603K"))
    )
    (comp (ref "C44")
      (value "100n")
      (footprint "eagle-import:C0603K")
      (libsource (lib "eagle-import") (part "C-EUC0603K"))
    )
    (comp (ref "C45")
      (value "100n")
      (footprint "eagle-import:C0603K")
      (libsource (lib "eagle-import") (part "C-EUC0603K"))
    )
    (comp (ref "C46")
      (value "100n")
      (footprint "eagle-import:C0603K")
      (libsource (lib "eagle-import") (part "C-EUC0603K"))
    )
    (comp (ref "C47")
      (value "100n")
      (footprint "eagle-import:C0603K")
      (libsource (lib "eagle-import") (part "C-EUC0603K"))
    )
    (comp (ref "C48")
      (value "100n")
      (footprint "eagle-import:C0603K")
      (libsource (lib "eagle-import") (part "C-EUC0603K"))
    )
    (comp (ref "C49")
      (value "100n")
      (footprint "eagle-import:C0603K")
      (libsource (lib "eagle-import") (part "C-EUC0603K"))
    )
    (comp (ref "C50")
      (value "10n")
      (footprint "eagle-import:C0603K")
      (libsource (lib "eagle-import") (part "C-EUC0603K"))
    )
    (comp (ref "IC1")
      (value "LPC1765")
      (footprint "eagle-import:LQFP100-14X14")
      (libsource (lib "eagle-import") (part "LPC1765"))
    )
    (comp (ref "IC2")
      (value "PROASIC3_NANO_A3PN125")
      (footprint "eagle-import:VQFP100")
      (libsource (lib "eagle-import") (part "PROASIC3_NANO_A3PN125"))
    )
    (comp (ref "JTAG_A3PN")
      (value "PINHD-2X05_2.54-SMD")
      (footprint "eagle-import:2X05SMD")
      (libsource (lib "eagle-import") (part "PINHD-2X05_2.54-SMD"))
    )
    (comp (ref "JTAG_LPC")
      (value "PINHD-2X10_2.54-SMD")
      (footprint "eagle-import:2X10SMD")
      (libsource (lib "eagle-import") (part "PINHD-2X10_2.54-SMD"))
    )
    (comp (ref "Q1")
      (value "12MHz")
      (footprint "eagle-import:CTS406")
      (libsource (lib "eagle-import") (part "CRYSTALCTS406"))
    )
    (comp (ref "R10")
      (value "10k")
      (footprint "eagle-import:R0603")
      (libsource (lib "eagle-import") (part "R-EU_R0603"))
    )
    (comp (ref "R11")
      (value "10k")
      (footprint "eagle-import:R0603")
      (libsource (lib "eagle-import") (part "R-EU_R0603"))
    )
    (comp (ref "R12")
      (value "10k")
      (footprint "eagle-import:R0603")
      (libsource (lib "eagle-import") (part "R-EU_R0603"))
    )
    (comp (ref "R13")
      (value "10k")
      (footprint "eagle-import:R0603")
      (libsource (lib "eagle-import") (part "R-EU_R0603"))
    )
    (comp (ref "R14")
      (value "10k")
      (footprint "eagle-import:R0603")
      (libsource (lib "eagle-import") (part "R-EU_R0603"))
    )
    (comp (ref "R15")
      (value "10k")
      (footprint "eagle-import:R0603")
      (libsource (lib "eagle-import") (part "R-EU_R0603"))
    )
    (comp (ref "R83")
      (value "10k")
      (footprint "eagle-import:R0603")
      (libsource (lib "eagle-import") (part "R-EU_R0603"))
    )
    (comp (ref "R84")
      (value "10k")
      (footprint "eagle-import:R0603")
      (libsource (lib "eagle-import") (part "R-EU_R0603"))
    )
    (comp (ref "C14")
      (value "47p")
      (footprint "eagle-import:C0603")
      (libsource (lib "eagle-import") (part "C-EUC0603"))
    )
    (comp (ref "C15")
      (value "47p")
      (footprint "eagle-import:C0603")
      (libsource (lib "eagle-import") (part "C-EUC0603"))
    )
    (comp (ref "C16")
      (value "100n")
      (footprint "eagle-import:C0603")
      (libsource (lib "eagle-import") (part "C-EUC0603"))
    )
    (comp (ref "C17")
      (value "10n")
      (footprint "eagle-import:C0603")
      (libsource (lib "eagle-import") (part "C-EUC0603"))
    )
    (comp (ref "C18")
      (value "100n")
      (footprint "eagle-import:C0603")
      (libsource (lib "eagle-import") (part "C-EUC0603"))
    )
    (comp (ref "C19")
      (value "TA 10u")
      (footprint "eagle-import:CT3216")
      (libsource (lib "eagle-import") (part "CPOL-EUCT3216"))
    )
    (comp (ref "FT230X")
      (value "SERIAL_FT230XQ")
      (footprint "eagle-import:SERIAL_QFN4X4-16")
      (libsource (lib "eagle-import") (part "SERIAL_FT230XQ"))
    )
    (comp (ref "ISP")
      (value "B3U-1000P")
      (footprint "eagle-import:B3U-1000P")
      (libsource (lib "eagle-import") (part "B3U-1000P"))
    )
    (comp (ref "L1")
      (value "10µH")
      (footprint "eagle-import:WE-KI_0805_B")
      (libsource (lib "eagle-import") (part "WE-KI_0805_B"))
    )
    (comp (ref "LED1")
      (value "RED")
      (footprint "eagle-import:CHIP-LED0603")
      (libsource (lib "eagle-import") (part "LEDCHIP-LED0603"))
    )
    (comp (ref "LED2")
      (value "RED")
      (footprint "eagle-import:CHIP-LED0603")
      (libsource (lib "eagle-import") (part "LEDCHIP-LED0603"))
    )
    (comp (ref "LED3")
      (value "RED")
      (footprint "eagle-import:CHIP-LED0603")
      (libsource (lib "eagle-import") (part "LEDCHIP-LED0603"))
    )
    (comp (ref "LED4")
      (value "RED")
      (footprint "eagle-import:CHIP-LED0603")
      (libsource (lib "eagle-import") (part "LEDCHIP-LED0603"))
    )
    (comp (ref "PWR_UP")
      (value "GREEN")
      (footprint "eagle-import:CHIPLED_0603")
      (libsource (lib "eagle-import") (part "LEDCHIPLED_0603"))
    )
    (comp (ref "R4")
      (value "270")
      (footprint "eagle-import:R0603")
      (libsource (lib "eagle-import") (part "R-EU_R0603"))
    )
    (comp (ref "R5")
      (value "270")
      (footprint "eagle-import:R0603")
      (libsource (lib "eagle-import") (part "R-EU_R0603"))
    )
    (comp (ref "R6")
      (value "270")
      (footprint "eagle-import:R0603")
      (libsource (lib "eagle-import") (part "R-EU_R0603"))
    )
    (comp (ref "R7")
      (value "270")
      (footprint "eagle-import:R0603")
      (libsource (lib "eagle-import") (part "R-EU_R0603"))
    )
    (comp (ref "R8")
      (value "47k")
      (footprint "eagle-import:R0603")
      (libsource (lib "eagle-import") (part "R-EU_R0603"))
    )
    (comp (ref "R9")
      (value "47k")
      (footprint "eagle-import:R0603")
      (libsource (lib "eagle-import") (part "R-EU_R0603"))
    )
    (comp (ref "R16")
      (value "680")
      (footprint "eagle-import:R0603")
      (libsource (lib "eagle-import") (part "resistor_R-EU_R0603"))
    )
    (comp (ref "R17")
      (value "27")
      (footprint "eagle-import:R0603")
      (libsource (lib "eagle-import") (part "resistor_R-EU_R0603"))
    )
    (comp (ref "R18")
      (value "27")
      (footprint "eagle-import:R0603")
      (libsource (lib "eagle-import") (part "resistor_R-EU_R0603"))
    )
    (comp (ref "RESET")
      (value "B3U-1000P")
      (footprint "eagle-import:B3U-1000P")
      (libsource (lib "eagle-import") (part "B3U-1000P"))
    )
    (comp (ref "X1")
      (value "USBSMD")
      (footprint "eagle-import:USB-MINIB")
      (libsource (lib "eagle-import") (part "USBSMD"))
    )
    (comp (ref "C1")
      (value "10u")
      (footprint "eagle-import:CT3216")
      (libsource (lib "eagle-import") (part "CPOL-EUCT3216"))
    )
    (comp (ref "C2")
      (value "47u")
      (footprint "eagle-import:CT3216")
      (libsource (lib "eagle-import") (part "CPOL-EUCT3216"))
    )
    (comp (ref "C30")
      (value "100n")
      (footprint "eagle-import:C0603K")
      (libsource (lib "eagle-import") (part "C-EUC0603K"))
    )
    (comp (ref "C31")
      (value "10u")
      (footprint "eagle-import:CT3216")
      (libsource (lib "eagle-import") (part "CPOL-EUCT3216"))
    )
    (comp (ref "C32")
      (value "47u")
      (footprint "eagle-import:CT3216")
      (libsource (lib "eagle-import") (part "CPOL-EUCT3216"))
    )
    (comp (ref "C33")
      (value "100n")
      (footprint "eagle-import:C0603K")
      (libsource (lib "eagle-import") (part "C-EUC0603K"))
    )
    (comp (ref "C35")
      (value "10u")
      (footprint "eagle-import:CT3216")
      (libsource (lib "eagle-import") (part "CPOL-EUCT3216"))
    )
    (comp (ref "C36")
      (value "47u")
      (footprint "eagle-import:CT3216")
      (libsource (lib "eagle-import") (part "CPOL-EUCT3216"))
    )
    (comp (ref "C37")
      (value "100n")
      (footprint "eagle-import:C0603K")
      (libsource (lib "eagle-import") (part "C-EUC0603K"))
    )
    (comp (ref "L2")
      (value "2.2uH")
      (footprint "eagle-import:VLS_INDUCTOR")
      (libsource (lib "eagle-import") (part "VLS201610E"))
    )
    (comp (ref "L3")
      (value "2.2uH")
      (footprint "eagle-import:VLS_INDUCTOR")
      (libsource (lib "eagle-import") (part "VLS201610E"))
    )
    (comp (ref "L4")
      (value "2.2uH")
      (footprint "eagle-import:VLS_INDUCTOR")
      (libsource (lib "eagle-import") (part "VLS201610E"))
    )
    (comp (ref "LM1")
      (value "LM3671_3V3IO")
      (footprint "eagle-import:SOT23-5L")
      (libsource (lib "eagle-import") (part "LM3671"))
    )
    (comp (ref "LM2")
      (value "LM3671_3V3_LPC")
      (footprint "eagle-import:SOT23-5L")
      (libsource (lib "eagle-import") (part "LM3671"))
    )
    (comp (ref "LM3671")
      (value "LM3671_1V5")
      (footprint "eagle-import:SOT23-5L")
      (libsource (lib "eagle-import") (part "LM3671"))
    )
  )
  (nets
    (net (code "18") (name "+5V") (class "Default")
      (node (ref "C17") (pin "2") (pinfunction "2_2") (pintype "passive"))
      (node (ref "C2") (pin "+") (pinfunction "+_+") (pintype "passive"))
      (node (ref "C32") (pin "+") (pinfunction "+_+") (pintype "passive"))
      (node (ref "C34") (pin "+") (pinfunction "+_+") (pintype "passive"))
      (node (ref "C51") (pin "+") (pinfunction "+_+") (pintype "passive"))
      (node (ref "C52") (pin "+") (pinfunction "+_+") (pintype "passive"))
      (node (ref "C53") (pin "+") (pinfunction "+_+") (pintype "passive"))
      (node (ref "C54") (pin "+") (pinfunction "+_+") (pintype "passive"))
      (node (ref "C55") (pin "+") (pinfunction "+_+") (pintype "passive"))
      (node (ref "C56") (pin "+") (pinfunction "+_+") (pintype "passive"))
      (node (ref "C57") (pin "+") (pinfunction "+_+") (pintype "passive"))
      (node (ref "CH1") (pin "P2") (pinfunction "P2_P2") (pintype "bidirectional"))
      (node (ref "CH2") (pin "P2") (pinfunction "P2_P2") (pintype "bidirectional"))
      (node (ref "CH3") (pin "P2") (pinfunction "P2_P2") (pintype "bidirectional"))
      (node (ref "CH4") (pin "P2") (pinfunction "P2_P2") (pintype "bidirectional"))
      (node (ref "CH5") (pin "P2") (pinfunction "P2_P2") (pintype "bidirectional"))
      (node (ref "CH6") (pin "P2") (pinfunction "P2_P2") (pintype "bidirectional"))
      (node (ref "CH7") (pin "P2") (pinfunction "P2_P2") (pintype "bidirectional"))
      (node (ref "CH8") (pin "P2") (pinfunction "P2_P2") (pintype "bidirectional"))
      (node (ref "L1") (pin "2") (pinfunction "1_2") (pintype "passive"))
      (node (ref "LM1") (pin "1") (pinfunction "VIN_1") (pintype "bidirectional"))
      (node (ref "LM2") (pin "1") (pinfunction "VIN_1") (pintype "bidirectional"))
      (node (ref "LM2") (pin "3") (pinfunction "EN_3") (pintype "bidirectional"))
      (node (ref "R16") (pin "2") (pinfunction "2_2") (pintype "passive"))
      (node (ref "TP10") (pin "TP") (pinfunction "TP_TP") (pintype "input"))
      (node (ref "TP11") (pin "TP") (pinfunction "TP_TP") (pintype "input"))
      (node (ref "X1") (pin "VBUS") (pinfunction "VBUS_VBUS") (pintype "bidirectional"))
    )
    (net (code "37") (name "BUT1") (class "Default")
      (node (ref "IC1") (pin "53") (pinfunction "P2[10]/EINT0/NMI_53") (pintype "bidirectional"))
      (node (ref "ISP") (pin "P$2") (pinfunction "1_P$2") (pintype "passive"))
      (node (ref "R9") (pin "1") (pinfunction "1_1") (pintype "passive"))
    )
    (net (code "38") (name "CH1_EN") (class "Default")
      (node (ref "C22") (pin "1") (pinfunction "1_1") (pintype "passive"))
      (node (ref "IC1") (pin "6") (pinfunction "P0[26]/AD0[3]/AOUT/RXD3_6") (pintype "bidirectional"))
      (node (ref "R36") (pin "1") (pinfunction "1_1") (pintype "passive"))
      (node (ref "U$5") (pin "P$15") (pinfunction "VREFB_P$15") (pintype "power_in"))
      (node (ref "U$5") (pin "P$16") (pinfunction "EN_P$16") (pintype "input"))
    )
    (net (code "39") (name "CH1_IA") (class "Default")
      (node (ref "HCH8") (pin "11") (pinfunction "11_11") (pintype "passive"))
      (node (ref "IC2") (pin "86") (pinfunction "IO19RSB0_86") (pintype "bidirectional"))
      (node (ref "R42") (pin "1") (pinfunction "1_1") (pintype "passive"))
      (node (ref "U$6") (pin "P$3") (pinfunction "A1_P$3") (pintype "bidirectional"))
    )
    (net (code "40") (name "CH1_IB") (class "Default")
      (node (ref "HCH8") (pin "7") (pinfunction "7_7") (pintype "passive"))
      (node (ref "IC2") (pin "91") (pinfunction "IO13RSB0_91") (pintype "bidirectional"))
      (node (ref "R40") (pin "1") (pinfunction "1_1") (pintype "passive"))
      (node (ref "U$6") (pin "P$5") (pinfunction "A3_P$5") (pintype "bidirectional"))
    )
    (net (code "41") (name "CH1_IC") (class "Default")
      (node (ref "HCH8") (pin "3") (pinfunction "3_3") (pintype "passive"))
      (node (ref "IC2") (pin "93") (pinfunction "IO09RSB0_93") (pintype "bidirectional"))
      (node (ref "R38") (pin "1") (pinfunction "1_1") (pintype "passive"))
      (node (ref "U$6") (pin "P$7") (pinfunction "A5_P$7") (pintype "bidirectional"))
    )
    (net (code "42") (name "CH1_OA") (class "Default")
      (node (ref "HCH8") (pin "9") (pinfunction "9_9") (pintype "passive"))
      (node (ref "IC2") (pin "90") (pinfunction "IO15RSB0_90") (pintype "bidirectional"))
      (node (ref "R41") (pin "1") (pinfunction "1_1") (pintype "passive"))
      (node (ref "U$6") (pin "P$4") (pinfunction "A2_P$4") (pintype "bidirectional"))
    )
    (net (code "43") (name "CH1_OB") (class "Default")
      (node (ref "HCH8") (pin "5") (pinfunction "5_5") (pintype "passive"))
      (node (ref "IC2") (pin "92") (pinfunction "IO11RSB0_92") (pintype "bidirectional"))
      (node (ref "R39") (pin "1") (pinfunction "1_1") (pintype "passive"))
      (node (ref "U$6") (pin "P$6") (pinfunction "A4_P$6") (pintype "bidirectional"))
    )
    (net (code "44") (name "CH1_OC") (class "Default")
      (node (ref "HCH8") (pin "1") (pinfunction "1_1") (pintype "passive"))
      (node (ref "IC2") (pin "94") (pinfunction "IO07RSB0_94") (pintype "bidirectional"))
      (node (ref "R37") (pin "1") (pinfunction "1_1") (pintype "passive"))
      (node (ref "U$6") (pin "P$8") (pinfunction "A6_P$8") (pintype "bidirectional"))
    )
    (net (code "45") (name "CH1_TIA") (class "Default")
      (node (ref "CH1") (pin "P3") (pinfunction "P3_P3") (pintype "bidirectional"))
      (node (ref "HCH1") (pin "12") (pinfunction "12_12") (pintype "passive"))
      (node (ref "U$5") (pin "P$14") (pinfunction "B1_P$14") (pintype "bidirectional"))
    )
    (net (code "46") (name "CH1_TIB") (class "Default")
      (node (ref "CH1") (pin "P5") (pinfunction "P5_P5") (pintype "bidirectional"))
      (node (ref "HCH1") (pin "8") (pinfunction "8_8") (pintype "passive"))
      (node (ref "U$5") (pin "P$12") (pinfunction "B3_P$12") (pintype "bidirectional"))
    )
    (net (code "47") (name "CH1_TIC") (class "Default")
      (node (ref "CH1") (pin "P7") (pinfunction "P7_P7") (pintype "bidirectional"))
      (node (ref "HCH1") (pin "4") (pinfunction "4_4") (pintype "passive"))
      (node (ref "U$5") (pin "P$10") (pinfunction "B5_P$10") (pintype "bidirectional"))
    )
    (net (code "48") (name "CH1_TOA") (class "Default")
      (node (ref "CH1") (pin "P4") (pinfunction "P4_P4") (pintype "bidirectional"))
      (node (ref "HCH1") (pin "10") (pinfunction "10_10") (pintype "passive"))
      (node (ref "U$5") (pin "P$13") (pinfunction "B2_P$13") (pintype "bidirectional"))
    )
    (net (code "49") (name "CH1_TOB") (class "Default")
      (node (ref "CH1") (pin "P6") (pinfunction "P6_P6") (pintype "bidirectional"))
      (node (ref "HCH1") (pin "6") (pinfunction "6_6") (pintype "passive"))
      (node (ref "U$5") (pin "P$11") (pinfunction "B4_P$11") (pintype "bidirectional"))
    )
    (net (code "50") (name "CH1_TOC") (class "Default")
      (node (ref "CH1") (pin "P8") (pinfunction "P8_P8") (pintype "bidirectional"))
      (node (ref "HCH1") (pin "2") (pinfunction "2_2") (pintype "passive"))
      (node (ref "U$5") (pin "P$9") (pinfunction "B6_P$9") (pintype "bidirectional"))
    )
    (net (code "51") (name "CH2_EN") (class "Default")
      (node (ref "C21") (pin "1") (pinfunction "1_1") (pintype "passive"))
      (node (ref "IC1") (pin "7") (pinfunction "P0[25]/AD0[2]/I2SRX_SDA/TXD3_7") (pintype "bidirectional"))
      (node (ref "R29") (pin "1") (pinfunction "1_1") (pintype "passive"))
      (node (ref "U$4") (pin "P$15") (pinfunction "VREFB_P$15") (pintype "power_in"))
      (node (ref "U$4") (pin "P$16") (pinfunction "EN_P$16") (pintype "input"))
    )
    (net (code "52") (name "CH2_IA") (class "Default")
      (node (ref "HCH1") (pin "11") (pinfunction "11_11") (pintype "passive"))
      (node (ref "IC2") (pin "26") (pinfunction "GEA2/IO106RSB1_26") (pintype "bidirectional"))
      (node (ref "R35") (pin "1") (pinfunction "1_1") (pintype "passive"))
      (node (ref "U$5") (pin "P$3") (pinfunction "A1_P$3") (pintype "bidirectional"))
    )
    (net (code "53") (name "CH2_IB") (class "Default")
      (node (ref "HCH1") (pin "7") (pinfunction "7_7") (pintype "passive"))
      (node (ref "IC2") (pin "28") (pinfunction "GEC2/IO104RSB1_28") (pintype "bidirectional"))
      (node (ref "R33") (pin "1") (pinfunction "1_1") (pintype "passive"))
      (node (ref "U$5") (pin "P$5") (pinfunction "A3_P$5") (pintype "bidirectional"))
    )
    (net (code "54") (name "CH2_IC") (class "Default")
      (node (ref "HCH1") (pin "3") (pinfunction "3_3") (pintype "passive"))
      (node (ref "IC2") (pin "30") (pinfunction "IO100RSB1_30") (pintype "bidirectional"))
      (node (ref "R31") (pin "1") (pinfunction "1_1") (pintype "passive"))
      (node (ref "U$5") (pin "P$7") (pinfunction "A5_P$7") (pintype "bidirectional"))
    )
    (net (code "55") (name "CH2_OA") (class "Default")
      (node (ref "HCH1") (pin "9") (pinfunction "9_9") (pintype "passive"))
      (node (ref "IC2") (pin "27") (pinfunction "GEB2/IO105RSB1_27") (pintype "bidirectional"))
      (node (ref "R34") (pin "1") (pinfunction "1_1") (pintype "passive"))
      (node (ref "U$5") (pin "P$4") (pinfunction "A2_P$4") (pintype "bidirectional"))
    )
    (net (code "56") (name "CH2_OB") (class "Default")
      (node (ref "HCH1") (pin "5") (pinfunction "5_5") (pintype "passive"))
      (node (ref "IC2") (pin "29") (pinfunction "IO102RSB1_29") (pintype "bidirectional"))
      (node (ref "R32") (pin "1") (pinfunction "1_1") (pintype "passive"))
      (node (ref "U$5") (pin "P$6") (pinfunction "A4_P$6") (pintype "bidirectional"))
    )
    (net (code "57") (name "CH2_OC") (class "Default")
      (node (ref "HCH1") (pin "1") (pinfunction "1_1") (pintype "passive"))
      (node (ref "IC2") (pin "31") (pinfunction "IO99RSB1_31") (pintype "bidirectional"))
      (node (ref "R30") (pin "1") (pinfunction "1_1") (pintype "passive"))
      (node (ref "U$5") (pin "P$8") (pinfunction "A6_P$8") (pintype "bidirectional"))
    )
    (net (code "58") (name "CH2_TIA") (class "Default")
      (node (ref "CH2") (pin "P3") (pinfunction "P3_P3") (pintype "bidirectional"))
      (node (ref "HCH2") (pin "12") (pinfunction "12_12") (pintype "passive"))
      (node (ref "U$4") (pin "P$14") (pinfunction "B1_P$14") (pintype "bidirectional"))
    )
    (net (code "59") (name "CH2_TIB") (class "Default")
      (node (ref "CH2") (pin "P5") (pinfunction "P5_P5") (pintype "bidirectional"))
      (node (ref "HCH2") (pin "8") (pinfunction "8_8") (pintype "passive"))
      (node (ref "U$4") (pin "P$12") (pinfunction "B3_P$12") (pintype "bidirectional"))
    )
    (net (code "60") (name "CH2_TIC") (class "Default")
      (node (ref "CH2") (pin "P7") (pinfunction "P7_P7") (pintype "bidirectional"))
      (node (ref "HCH2") (pin "4") (pinfunction "4_4") (pintype "passive"))
      (node (ref "U$4") (pin "P$10") (pinfunction "B5_P$10") (pintype "bidirectional"))
    )
    (net (code "61") (name "CH2_TOA") (class "Default")
      (node (ref "CH2") (pin "P4") (pinfunction "P4_P4") (pintype "bidirectional"))
      (node (ref "HCH2") (pin "10") (pinfunction "10_10") (pintype "passive"))
      (node (ref "U$4") (pin "P$13") (pinfunction "B2_P$13") (pintype "bidirectional"))
    )
    (net (code "62") (name "CH2_TOB") (class "Default")
      (node (ref "CH2") (pin "P6") (pinfunction "P6_P6") (pintype "bidirectional"))
      (node (ref "HCH2") (pin "6") (pinfunction "6_6") (pintype "passive"))
      (node (ref "U$4") (pin "P$11") (pinfunction "B4_P$11") (pintype "bidirectional"))
    )
    (net (code "63") (name "CH2_TOC") (class "Default")
      (node (ref "CH2") (pin "P8") (pinfunction "P8_P8") (pintype "bidirectional"))
      (node (ref "HCH2") (pin "2") (pinfunction "2_2") (pintype "passive"))
      (node (ref "U$4") (pin "P$9") (pinfunction "B6_P$9") (pintype "bidirectional"))
    )
    (net (code "64") (name "CH3_EN") (class "Default")
      (node (ref "C20") (pin "1") (pinfunction "1_1") (pintype "passive"))
      (node (ref "IC1") (pin "8") (pinfunction "P0[24]/AD0[1]/I2SRX_WS/CAP3[1]_8") (pintype "bidirectional"))
      (node (ref "R22") (pin "1") (pinfunction "1_1") (pintype "passive"))
      (node (ref "U$3") (pin "P$15") (pinfunction "VREFB_P$15") (pintype "power_in"))
      (node (ref "U$3") (pin "P$16") (pinfunction "EN_P$16") (pintype "input"))
    )
    (net (code "65") (name "CH3_IA") (class "Default")
      (node (ref "HCH2") (pin "11") (pinfunction "11_11") (pintype "passive"))
      (node (ref "IC2") (pin "32") (pinfunction "IO97RSB1_32") (pintype "bidirectional"))
      (node (ref "R28") (pin "1") (pinfunction "1_1") (pintype "passive"))
      (node (ref "U$4") (pin "P$3") (pinfunction "A1_P$3") (pintype "bidirectional"))
    )
    (net (code "66") (name "CH3_IB") (class "Default")
      (node (ref "HCH2") (pin "7") (pinfunction "7_7") (pintype "passive"))
      (node (ref "IC2") (pin "34") (pinfunction "IO95RSB1_34") (pintype "bidirectional"))
      (node (ref "R26") (pin "1") (pinfunction "1_1") (pintype "passive"))
      (node (ref "U$4") (pin "P$5") (pinfunction "A3_P$5") (pintype "bidirectional"))
    )
    (net (code "67") (name "CH3_IC") (class "Default")
      (node (ref "HCH2") (pin "3") (pinfunction "3_3") (pintype "passive"))
      (node (ref "IC2") (pin "36") (pinfunction "IO93RSB1_36") (pintype "bidirectional"))
      (node (ref "R24") (pin "1") (pinfunction "1_1") (pintype "passive"))
      (node (ref "U$4") (pin "P$7") (pinfunction "A5_P$7") (pintype "bidirectional"))
    )
    (net (code "68") (name "CH3_OA") (class "Default")
      (node (ref "HCH2") (pin "9") (pinfunction "9_9") (pintype "passive"))
      (node (ref "IC2") (pin "33") (pinfunction "IO96RSB1_33") (pintype "bidirectional"))
      (node (ref "R27") (pin "1") (pinfunction "1_1") (pintype "passive"))
      (node (ref "U$4") (pin "P$4") (pinfunction "A2_P$4") (pintype "bidirectional"))
    )
    (net (code "69") (name "CH3_OB") (class "Default")
      (node (ref "HCH2") (pin "5") (pinfunction "5_5") (pintype "passive"))
      (node (ref "IC2") (pin "35") (pinfunction "IO94RSB1_35") (pintype "bidirectional"))
      (node (ref "R25") (pin "1") (pinfunction "1_1") (pintype "passive"))
      (node (ref "U$4") (pin "P$6") (pinfunction "A4_P$6") (pintype "bidirectional"))
    )
    (net (code "70") (name "CH3_OC") (class "Default")
      (node (ref "HCH2") (pin "1") (pinfunction "1_1") (pintype "passive"))
      (node (ref "IC2") (pin "40") (pinfunction "IO87RSB1_40") (pintype "bidirectional"))
      (node (ref "R23") (pin "1") (pinfunction "1_1") (pintype "passive"))
      (node (ref "U$4") (pin "P$8") (pinfunction "A6_P$8") (pintype "bidirectional"))
    )
    (net (code "71") (name "CH3_TIA") (class "Default")
      (node (ref "CH3") (pin "P3") (pinfunction "P3_P3") (pintype "bidirectional"))
      (node (ref "HCH3") (pin "12") (pinfunction "12_12") (pintype "passive"))
      (node (ref "U$3") (pin "P$14") (pinfunction "B1_P$14") (pintype "bidirectional"))
    )
    (net (code "72") (name "CH3_TIB") (class "Default")
      (node (ref "CH3") (pin "P5") (pinfunction "P5_P5") (pintype "bidirectional"))
      (node (ref "HCH3") (pin "8") (pinfunction "8_8") (pintype "passive"))
      (node (ref "U$3") (pin "P$12") (pinfunction "B3_P$12") (pintype "bidirectional"))
    )
    (net (code "73") (name "CH3_TIC") (class "Default")
      (node (ref "CH3") (pin "P7") (pinfunction "P7_P7") (pintype "bidirectional"))
      (node (ref "HCH3") (pin "4") (pinfunction "4_4") (pintype "passive"))
      (node (ref "U$3") (pin "P$10") (pinfunction "B5_P$10") (pintype "bidirectional"))
    )
    (net (code "74") (name "CH3_TOA") (class "Default")
      (node (ref "CH3") (pin "P4") (pinfunction "P4_P4") (pintype "bidirectional"))
      (node (ref "HCH3") (pin "10") (pinfunction "10_10") (pintype "passive"))
      (node (ref "U$3") (pin "P$13") (pinfunction "B2_P$13") (pintype "bidirectional"))
    )
    (net (code "75") (name "CH3_TOB") (class "Default")
      (node (ref "CH3") (pin "P6") (pinfunction "P6_P6") (pintype "bidirectional"))
      (node (ref "HCH3") (pin "6") (pinfunction "6_6") (pintype "passive"))
      (node (ref "U$3") (pin "P$11") (pinfunction "B4_P$11") (pintype "bidirectional"))
    )
    (net (code "76") (name "CH3_TOC") (class "Default")
      (node (ref "CH3") (pin "P8") (pinfunction "P8_P8") (pintype "bidirectional"))
      (node (ref "HCH3") (pin "2") (pinfunction "2_2") (pintype "passive"))
      (node (ref "U$3") (pin "P$9") (pinfunction "B6_P$9") (pintype "bidirectional"))
    )
    (net (code "77") (name "CH4_EN") (class "Default")
      (node (ref "C24") (pin "1") (pinfunction "1_1") (pintype "passive"))
      (node (ref "IC1") (pin "9") (pinfunction "P0[23]/AD0[0]/I2SRX_CLK/CAP3[0]_9") (pintype "bidirectional"))
      (node (ref "R50") (pin "1") (pinfunction "1_1") (pintype "passive"))
      (node (ref "U$7") (pin "P$15") (pinfunction "VREFB_P$15") (pintype "power_in"))
      (node (ref "U$7") (pin "P$16") (pinfunction "EN_P$16") (pintype "input"))
    )
    (net (code "78") (name "CH4_IA") (class "Default")
      (node (ref "HCH3") (pin "11") (pinfunction "11_11") (pintype "passive"))
      (node (ref "IC2") (pin "41") (pinfunction "IO84RSB1_41") (pintype "bidirectional"))
      (node (ref "R1") (pin "1") (pinfunction "1_1") (pintype "passive"))
      (node (ref "U$3") (pin "P$3") (pinfunction "A1_P$3") (pintype "bidirectional"))
    )
    (net (code "79") (name "CH4_IB") (class "Default")
      (node (ref "HCH3") (pin "7") (pinfunction "7_7") (pintype "passive"))
      (node (ref "IC2") (pin "43") (pinfunction "IO75RSB1_43") (pintype "bidirectional"))
      (node (ref "R3") (pin "1") (pinfunction "1_1") (pintype "passive"))
      (node (ref "U$3") (pin "P$5") (pinfunction "A3_P$5") (pintype "bidirectional"))
    )
    (net (code "80") (name "CH4_IC") (class "Default")
      (node (ref "HCH3") (pin "3") (pinfunction "3_3") (pintype "passive"))
      (node (ref "IC2") (pin "45") (pinfunction "GDB2/IO71RSB1_45") (pintype "bidirectional"))
      (node (ref "R20") (pin "1") (pinfunction "1_1") (pintype "passive"))
      (node (ref "U$3") (pin "P$7") (pinfunction "A5_P$7") (pintype "bidirectional"))
    )
    (net (code "81") (name "CH4_OA") (class "Default")
      (node (ref "HCH3") (pin "9") (pinfunction "9_9") (pintype "passive"))
      (node (ref "IC2") (pin "42") (pinfunction "IO81RSB1_42") (pintype "bidirectional"))
      (node (ref "R2") (pin "1") (pinfunction "1_1") (pintype "passive"))
      (node (ref "U$3") (pin "P$4") (pinfunction "A2_P$4") (pintype "bidirectional"))
    )
    (net (code "82") (name "CH4_OB") (class "Default")
      (node (ref "HCH3") (pin "5") (pinfunction "5_5") (pintype "passive"))
      (node (ref "IC2") (pin "44") (pinfunction "GDC2/IO72RSB1_44") (pintype "bidirectional"))
      (node (ref "R19") (pin "1") (pinfunction "1_1") (pintype "passive"))
      (node (ref "U$3") (pin "P$6") (pinfunction "A4_P$6") (pintype "bidirectional"))
    )
    (net (code "83") (name "CH4_OC") (class "Default")
      (node (ref "HCH3") (pin "1") (pinfunction "1_1") (pintype "passive"))
      (node (ref "IC2") (pin "46") (pinfunction "GDA2/IO70RSB1_46") (pintype "bidirectional"))
      (node (ref "R21") (pin "1") (pinfunction "1_1") (pintype "passive"))
      (node (ref "U$3") (pin "P$8") (pinfunction "A6_P$8") (pintype "bidirectional"))
    )
    (net (code "84") (name "CH4_TIA") (class "Default")
      (node (ref "CH4") (pin "P3") (pinfunction "P3_P3") (pintype "bidirectional"))
      (node (ref "HCH4") (pin "12") (pinfunction "12_12") (pintype "passive"))
      (node (ref "U$7") (pin "P$14") (pinfunction "B1_P$14") (pintype "bidirectional"))
    )
    (net (code "85") (name "CH4_TIB") (class "Default")
      (node (ref "CH4") (pin "P5") (pinfunction "P5_P5") (pintype "bidirectional"))
      (node (ref "HCH4") (pin "8") (pinfunction "8_8") (pintype "passive"))
      (node (ref "U$7") (pin "P$12") (pinfunction "B3_P$12") (pintype "bidirectional"))
    )
    (net (code "86") (name "CH4_TIC") (class "Default")
      (node (ref "CH4") (pin "P7") (pinfunction "P7_P7") (pintype "bidirectional"))
      (node (ref "HCH4") (pin "4") (pinfunction "4_4") (pintype "passive"))
      (node (ref "U$7") (pin "P$10") (pinfunction "B5_P$10") (pintype "bidirectional"))
    )
    (net (code "87") (name "CH4_TOA") (class "Default")
      (node (ref "CH4") (pin "P4") (pinfunction "P4_P4") (pintype "bidirectional"))
      (node (ref "HCH4") (pin "10") (pinfunction "10_10") (pintype "passive"))
      (node (ref "U$7") (pin "P$13") (pinfunction "B2_P$13") (pintype "bidirectional"))
    )
    (net (code "88") (name "CH4_TOB") (class "Default")
      (node (ref "CH4") (pin "P6") (pinfunction "P6_P6") (pintype "bidirectional"))
      (node (ref "HCH4") (pin "6") (pinfunction "6_6") (pintype "passive"))
      (node (ref "U$7") (pin "P$11") (pinfunction "B4_P$11") (pintype "bidirectional"))
    )
    (net (code "89") (name "CH4_TOC") (class "Default")
      (node (ref "CH4") (pin "P8") (pinfunction "P8_P8") (pintype "bidirectional"))
      (node (ref "HCH4") (pin "2") (pinfunction "2_2") (pintype "passive"))
      (node (ref "U$7") (pin "P$9") (pinfunction "B6_P$9") (pintype "bidirectional"))
    )
    (net (code "90") (name "CH5_EN") (class "Default")
      (node (ref "C25") (pin "1") (pinfunction "1_1") (pintype "passive"))
      (node (ref "IC1") (pin "51") (pinfunction "P2[12]/EINT2/I2STX_WS_51") (pintype "bidirectional"))
      (node (ref "R57") (pin "1") (pinfunction "1_1") (pintype "passive"))
      (node (ref "U$8") (pin "P$15") (pinfunction "VREFB_P$15") (pintype "power_in"))
      (node (ref "U$8") (pin "P$16") (pinfunction "EN_P$16") (pintype "input"))
    )
    (net (code "91") (name "CH5_IA") (class "Default")
      (node (ref "HCH4") (pin "11") (pinfunction "11_11") (pintype "passive"))
      (node (ref "IC2") (pin "57") (pinfunction "GDA1/IO65RSB0_57") (pintype "bidirectional"))
      (node (ref "R49") (pin "1") (pinfunction "1_1") (pintype "passive"))
      (node (ref "U$7") (pin "P$3") (pinfunction "A1_P$3") (pintype "bidirectional"))
    )
    (net (code "92") (name "CH5_IB") (class "Default")
      (node (ref "HCH4") (pin "7") (pinfunction "7_7") (pintype "passive"))
      (node (ref "IC2") (pin "59") (pinfunction "GDC1/IO61RSB0_59") (pintype "bidirectional"))
      (node (ref "R47") (pin "1") (pinfunction "1_1") (pintype "passive"))
      (node (ref "U$7") (pin "P$5") (pinfunction "A3_P$5") (pintype "bidirectional"))
    )
    (net (code "93") (name "CH5_IC") (class "Default")
      (node (ref "HCH4") (pin "3") (pinfunction "3_3") (pintype "passive"))
      (node (ref "IC2") (pin "61") (pinfunction "GCB2/IO58RSB0_61") (pintype "bidirectional"))
      (node (ref "R45") (pin "1") (pinfunction "1_1") (pintype "passive"))
      (node (ref "U$7") (pin "P$7") (pinfunction "A5_P$7") (pintype "bidirectional"))
    )
    (net (code "94") (name "CH5_OA") (class "Default")
      (node (ref "HCH4") (pin "9") (pinfunction "9_9") (pintype "passive"))
      (node (ref "IC2") (pin "58") (pinfunction "GDC0/IO62RSB0_58") (pintype "bidirectional"))
      (node (ref "R48") (pin "1") (pinfunction "1_1") (pintype "passive"))
      (node (ref "U$7") (pin "P$4") (pinfunction "A2_P$4") (pintype "bidirectional"))
    )
    (net (code "95") (name "CH5_OB") (class "Default")
      (node (ref "HCH4") (pin "5") (pinfunction "5_5") (pintype "passive"))
      (node (ref "IC2") (pin "60") (pinfunction "GCC2/IO59RSB0_60") (pintype "bidirectional"))
      (node (ref "R46") (pin "1") (pinfunction "1_1") (pintype "passive"))
      (node (ref "U$7") (pin "P$6") (pinfunction "A4_P$6") (pintype "bidirectional"))
    )
    (net (code "96") (name "CH5_OC") (class "Default")
      (node (ref "HCH4") (pin "1") (pinfunction "1_1") (pintype "passive"))
      (node (ref "IC2") (pin "62") (pinfunction "GCA0/IO56RSB0_62") (pintype "bidirectional"))
      (node (ref "R44") (pin "1") (pinfunction "1_1") (pintype "passive"))
      (node (ref "U$7") (pin "P$8") (pinfunction "A6_P$8") (pintype "bidirectional"))
    )
    (net (code "97") (name "CH5_TIA") (class "Default")
      (node (ref "CH5") (pin "P3") (pinfunction "P3_P3") (pintype "bidirectional"))
      (node (ref "HCH5") (pin "12") (pinfunction "12_12") (pintype "passive"))
      (node (ref "U$8") (pin "P$14") (pinfunction "B1_P$14") (pintype "bidirectional"))
    )
    (net (code "98") (name "CH5_TIB") (class "Default")
      (node (ref "CH5") (pin "P5") (pinfunction "P5_P5") (pintype "bidirectional"))
      (node (ref "HCH5") (pin "8") (pinfunction "8_8") (pintype "passive"))
      (node (ref "U$8") (pin "P$12") (pinfunction "B3_P$12") (pintype "bidirectional"))
    )
    (net (code "99") (name "CH5_TIC") (class "Default")
      (node (ref "CH5") (pin "P7") (pinfunction "P7_P7") (pintype "bidirectional"))
      (node (ref "HCH5") (pin "4") (pinfunction "4_4") (pintype "passive"))
      (node (ref "U$8") (pin "P$10") (pinfunction "B5_P$10") (pintype "bidirectional"))
    )
    (net (code "100") (name "CH5_TOA") (class "Default")
      (node (ref "CH5") (pin "P4") (pinfunction "P4_P4") (pintype "bidirectional"))
      (node (ref "HCH5") (pin "10") (pinfunction "10_10") (pintype "passive"))
      (node (ref "U$8") (pin "P$13") (pinfunction "B2_P$13") (pintype "bidirectional"))
    )
    (net (code "101") (name "CH5_TOB") (class "Default")
      (node (ref "CH5") (pin "P6") (pinfunction "P6_P6") (pintype "bidirectional"))
      (node (ref "HCH5") (pin "6") (pinfunction "6_6") (pintype "passive"))
      (node (ref "U$8") (pin "P$11") (pinfunction "B4_P$11") (pintype "bidirectional"))
    )
    (net (code "102") (name "CH5_TOC") (class "Default")
      (node (ref "CH5") (pin "P8") (pinfunction "P8_P8") (pintype "bidirectional"))
      (node (ref "HCH5") (pin "2") (pinfunction "2_2") (pintype "passive"))
      (node (ref "U$8") (pin "P$9") (pinfunction "B6_P$9") (pintype "bidirectional"))
    )
    (net (code "103") (name "CH6_EN") (class "Default")
      (node (ref "C26") (pin "1") (pinfunction "1_1") (pintype "passive"))
      (node (ref "IC1") (pin "52") (pinfunction "P2[11]/EINT1/I2STX_CLK_52") (pintype "bidirectional"))
      (node (ref "R64") (pin "1") (pinfunction "1_1") (pintype "passive"))
      (node (ref "U$9") (pin "P$15") (pinfunction "VREFB_P$15") (pintype "power_in"))
      (node (ref "U$9") (pin "P$16") (pinfunction "EN_P$16") (pintype "input"))
    )
    (net (code "104") (name "CH6_IA") (class "Default")
      (node (ref "HCH5") (pin "11") (pinfunction "11_11") (pintype "passive"))
      (node (ref "IC2") (pin "63") (pinfunction "GCA1/IO55RSB0_63") (pintype "bidirectional"))
      (node (ref "R56") (pin "1") (pinfunction "1_1") (pintype "passive"))
      (node (ref "U$8") (pin "P$3") (pinfunction "A1_P$3") (pintype "bidirectional"))
    )
    (net (code "105") (name "CH6_IB") (class "Default")
      (node (ref "HCH5") (pin "7") (pinfunction "7_7") (pintype "passive"))
      (node (ref "IC2") (pin "65") (pinfunction "GCC1/IO51RSB0_65") (pintype "bidirectional"))
      (node (ref "R54") (pin "1") (pinfunction "1_1") (pintype "passive"))
      (node (ref "U$8") (pin "P$5") (pinfunction "A3_P$5") (pintype "bidirectional"))
    )
    (net (code "106") (name "CH6_IC") (class "Default")
      (node (ref "HCH5") (pin "3") (pinfunction "3_3") (pintype "passive"))
      (node (ref "IC2") (pin "70") (pinfunction "GBC2/IO45RSB0_70") (pintype "bidirectional"))
      (node (ref "R52") (pin "1") (pinfunction "1_1") (pintype "passive"))
      (node (ref "U$8") (pin "P$7") (pinfunction "A5_P$7") (pintype "bidirectional"))
    )
    (net (code "107") (name "CH6_OA") (class "Default")
      (node (ref "HCH5") (pin "9") (pinfunction "9_9") (pintype "passive"))
      (node (ref "IC2") (pin "64") (pinfunction "GCC0/IO52RSB0_64") (pintype "bidirectional"))
      (node (ref "R55") (pin "1") (pinfunction "1_1") (pintype "passive"))
      (node (ref "U$8") (pin "P$4") (pinfunction "A2_P$4") (pintype "bidirectional"))
    )
    (net (code "108") (name "CH6_OB") (class "Default")
      (node (ref "HCH5") (pin "5") (pinfunction "5_5") (pintype "passive"))
      (node (ref "IC2") (pin "69") (pinfunction "IO47RSB0_69") (pintype "bidirectional"))
      (node (ref "R53") (pin "1") (pinfunction "1_1") (pintype "passive"))
      (node (ref "U$8") (pin "P$6") (pinfunction "A4_P$6") (pintype "bidirectional"))
    )
    (net (code "109") (name "CH6_OC") (class "Default")
      (node (ref "HCH5") (pin "1") (pinfunction "1_1") (pintype "passive"))
      (node (ref "IC2") (pin "71") (pinfunction "GBB2/IO43RSB0_71") (pintype "bidirectional"))
      (node (ref "R51") (pin "1") (pinfunction "1_1") (pintype "passive"))
      (node (ref "U$8") (pin "P$8") (pinfunction "A6_P$8") (pintype "bidirectional"))
    )
    (net (code "110") (name "CH6_TIA") (class "Default")
      (node (ref "CH6") (pin "P3") (pinfunction "P3_P3") (pintype "bidirectional"))
      (node (ref "HCH6") (pin "12") (pinfunction "12_12") (pintype "passive"))
      (node (ref "U$9") (pin "P$14") (pinfunction "B1_P$14") (pintype "bidirectional"))
    )
    (net (code "111") (name "CH6_TIB") (class "Default")
      (node (ref "CH6") (pin "P5") (pinfunction "P5_P5") (pintype "bidirectional"))
      (node (ref "HCH6") (pin "8") (pinfunction "8_8") (pintype "passive"))
      (node (ref "U$9") (pin "P$12") (pinfunction "B3_P$12") (pintype "bidirectional"))
    )
    (net (code "112") (name "CH6_TIC") (class "Default")
      (node (ref "CH6") (pin "P7") (pinfunction "P7_P7") (pintype "bidirectional"))
      (node (ref "HCH6") (pin "4") (pinfunction "4_4") (pintype "passive"))
      (node (ref "U$9") (pin "P$10") (pinfunction "B5_P$10") (pintype "bidirectional"))
    )
    (net (code "113") (name "CH6_TOA") (class "Default")
      (node (ref "CH6") (pin "P4") (pinfunction "P4_P4") (pintype "bidirectional"))
      (node (ref "HCH6") (pin "10") (pinfunction "10_10") (pintype "passive"))
      (node (ref "U$9") (pin "P$13") (pinfunction "B2_P$13") (pintype "bidirectional"))
    )
    (net (code "114") (name "CH6_TOB") (class "Default")
      (node (ref "CH6") (pin "P6") (pinfunction "P6_P6") (pintype "bidirectional"))
      (node (ref "HCH6") (pin "6") (pinfunction "6_6") (pintype "passive"))
      (node (ref "U$9") (pin "P$11") (pinfunction "B4_P$11") (pintype "bidirectional"))
    )
    (net (code "115") (name "CH6_TOC") (class "Default")
      (node (ref "CH6") (pin "P8") (pinfunction "P8_P8") (pintype "bidirectional"))
      (node (ref "HCH6") (pin "2") (pinfunction "2_2") (pintype "passive"))
      (node (ref "U$9") (pin "P$9") (pinfunction "B6_P$9") (pintype "bidirectional"))
    )
    (net (code "116") (name "CH7_EN") (class "Default")
      (node (ref "C27") (pin "1") (pinfunction "1_1") (pintype "passive"))
      (node (ref "IC1") (pin "58") (pinfunction "P0[20]/DTR1/SCL1_58") (pintype "bidirectional"))
      (node (ref "R71") (pin "1") (pinfunction "1_1") (pintype "passive"))
      (node (ref "U$10") (pin "P$15") (pinfunction "VREFB_P$15") (pintype "power_in"))
      (node (ref "U$10") (pin "P$16") (pinfunction "EN_P$16") (pintype "input"))
    )
    (net (code "117") (name "CH7_IA") (class "Default")
      (node (ref "HCH6") (pin "11") (pinfunction "11_11") (pintype "passive"))
      (node (ref "IC2") (pin "72") (pinfunction "IO42RSB0_72") (pintype "bidirectional"))
      (node (ref "R63") (pin "1") (pinfunction "1_1") (pintype "passive"))
      (node (ref "U$9") (pin "P$3") (pinfunction "A1_P$3") (pintype "bidirectional"))
    )
    (net (code "118") (name "CH7_IB") (class "Default")
      (node (ref "HCH6") (pin "7") (pinfunction "7_7") (pintype "passive"))
      (node (ref "IC2") (pin "76") (pinfunction "GBA1/IO40RSB0_76") (pintype "bidirectional"))
      (node (ref "R61") (pin "1") (pinfunction "1_1") (pintype "passive"))
      (node (ref "U$9") (pin "P$5") (pinfunction "A3_P$5") (pintype "bidirectional"))
    )
    (net (code "119") (name "CH7_IC") (class "Default")
      (node (ref "HCH6") (pin "3") (pinfunction "3_3") (pintype "passive"))
      (node (ref "IC2") (pin "78") (pinfunction "GBB1/IO38RSB0_78") (pintype "bidirectional"))
      (node (ref "R59") (pin "1") (pinfunction "1_1") (pintype "passive"))
      (node (ref "U$9") (pin "P$7") (pinfunction "A5_P$7") (pintype "bidirectional"))
    )
    (net (code "120") (name "CH7_OA") (class "Default")
      (node (ref "HCH6") (pin "9") (pinfunction "9_9") (pintype "passive"))
      (node (ref "IC2") (pin "73") (pinfunction "GBA2/IO41RSB0_73") (pintype "bidirectional"))
      (node (ref "R62") (pin "1") (pinfunction "1_1") (pintype "passive"))
      (node (ref "U$9") (pin "P$4") (pinfunction "A2_P$4") (pintype "bidirectional"))
    )
    (net (code "121") (name "CH7_OB") (class "Default")
      (node (ref "HCH6") (pin "5") (pinfunction "5_5") (pintype "passive"))
      (node (ref "IC2") (pin "77") (pinfunction "GBA0/IO39RSB0_77") (pintype "bidirectional"))
      (node (ref "R60") (pin "1") (pinfunction "1_1") (pintype "passive"))
      (node (ref "U$9") (pin "P$6") (pinfunction "A4_P$6") (pintype "bidirectional"))
    )
    (net (code "122") (name "CH7_OC") (class "Default")
      (node (ref "HCH6") (pin "1") (pinfunction "1_1") (pintype "passive"))
      (node (ref "IC2") (pin "79") (pinfunction "GBB0/IO37RSB0_79") (pintype "bidirectional"))
      (node (ref "R58") (pin "1") (pinfunction "1_1") (pintype "passive"))
      (node (ref "U$9") (pin "P$8") (pinfunction "A6_P$8") (pintype "bidirectional"))
    )
    (net (code "123") (name "CH7_TIA") (class "Default")
      (node (ref "CH7") (pin "P3") (pinfunction "P3_P3") (pintype "bidirectional"))
      (node (ref "HCH7") (pin "12") (pinfunction "12_12") (pintype "passive"))
      (node (ref "U$10") (pin "P$14") (pinfunction "B1_P$14") (pintype "bidirectional"))
    )
    (net (code "124") (name "CH7_TIB") (class "Default")
      (node (ref "CH7") (pin "P5") (pinfunction "P5_P5") (pintype "bidirectional"))
      (node (ref "HCH7") (pin "8") (pinfunction "8_8") (pintype "passive"))
      (node (ref "U$10") (pin "P$12") (pinfunction "B3_P$12") (pintype "bidirectional"))
    )
    (net (code "125") (name "CH7_TIC") (class "Default")
      (node (ref "CH7") (pin "P7") (pinfunction "P7_P7") (pintype "bidirectional"))
      (node (ref "HCH7") (pin "4") (pinfunction "4_4") (pintype "passive"))
      (node (ref "U$10") (pin "P$10") (pinfunction "B5_P$10") (pintype "bidirectional"))
    )
    (net (code "126") (name "CH7_TOA") (class "Default")
      (node (ref "CH7") (pin "P4") (pinfunction "P4_P4") (pintype "bidirectional"))
      (node (ref "HCH7") (pin "10") (pinfunction "10_10") (pintype "passive"))
      (node (ref "U$10") (pin "P$13") (pinfunction "B2_P$13") (pintype "bidirectional"))
    )
    (net (code "127") (name "CH7_TOB") (class "Default")
      (node (ref "CH7") (pin "P6") (pinfunction "P6_P6") (pintype "bidirectional"))
      (node (ref "HCH7") (pin "6") (pinfunction "6_6") (pintype "passive"))
      (node (ref "U$10") (pin "P$11") (pinfunction "B4_P$11") (pintype "bidirectional"))
    )
    (net (code "128") (name "CH7_TOC") (class "Default")
      (node (ref "CH7") (pin "P8") (pinfunction "P8_P8") (pintype "bidirectional"))
      (node (ref "HCH7") (pin "2") (pinfunction "2_2") (pintype "passive"))
      (node (ref "U$10") (pin "P$9") (pinfunction "B6_P$9") (pintype "bidirectional"))
    )
    (net (code "129") (name "CH8_EN") (class "Default")
      (node (ref "C23") (pin "1") (pinfunction "1_1") (pintype "passive"))
      (node (ref "IC1") (pin "59") (pinfunction "P0[19]/DSR1/SDA1_59") (pintype "bidirectional"))
      (node (ref "R43") (pin "1") (pinfunction "1_1") (pintype "passive"))
      (node (ref "U$6") (pin "P$15") (pinfunction "VREFB_P$15") (pintype "power_in"))
      (node (ref "U$6") (pin "P$16") (pinfunction "EN_P$16") (pintype "input"))
    )
    (net (code "130") (name "CH8_IA") (class "Default")
      (node (ref "HCH7") (pin "11") (pinfunction "11_11") (pintype "passive"))
      (node (ref "IC2") (pin "80") (pinfunction "GBC1/IO36RSB0_80") (pintype "bidirectional"))
      (node (ref "R70") (pin "1") (pinfunction "1_1") (pintype "passive"))
      (node (ref "U$10") (pin "P$3") (pinfunction "A1_P$3") (pintype "bidirectional"))
    )
    (net (code "131") (name "CH8_IB") (class "Default")
      (node (ref "HCH7") (pin "7") (pinfunction "7_7") (pintype "passive"))
      (node (ref "IC2") (pin "82") (pinfunction "IO32RSB0_82") (pintype "bidirectional"))
      (node (ref "R68") (pin "1") (pinfunction "1_1") (pintype "passive"))
      (node (ref "U$10") (pin "P$5") (pinfunction "A3_P$5") (pintype "bidirectional"))
    )
    (net (code "132") (name "CH8_IC") (class "Default")
      (node (ref "HCH7") (pin "3") (pinfunction "3_3") (pintype "passive"))
      (node (ref "IC2") (pin "84") (pinfunction "IO25RSB0_84") (pintype "bidirectional"))
      (node (ref "R66") (pin "1") (pinfunction "1_1") (pintype "passive"))
      (node (ref "U$10") (pin "P$7") (pinfunction "A5_P$7") (pintype "bidirectional"))
    )
    (net (code "133") (name "CH8_OA") (class "Default")
      (node (ref "HCH7") (pin "9") (pinfunction "9_9") (pintype "passive"))
      (node (ref "IC2") (pin "81") (pinfunction "GBC0/IO35RSB0_81") (pintype "bidirectional"))
      (node (ref "R69") (pin "1") (pinfunction "1_1") (pintype "passive"))
      (node (ref "U$10") (pin "P$4") (pinfunction "A2_P$4") (pintype "bidirectional"))
    )
    (net (code "134") (name "CH8_OB") (class "Default")
      (node (ref "HCH7") (pin "5") (pinfunction "5_5") (pintype "passive"))
      (node (ref "IC2") (pin "83") (pinfunction "IO28RSB0_83") (pintype "bidirectional"))
      (node (ref "R67") (pin "1") (pinfunction "1_1") (pintype "passive"))
      (node (ref "U$10") (pin "P$6") (pinfunction "A4_P$6") (pintype "bidirectional"))
    )
    (net (code "135") (name "CH8_OC") (class "Default")
      (node (ref "HCH7") (pin "1") (pinfunction "1_1") (pintype "passive"))
      (node (ref "IC2") (pin "85") (pinfunction "IO22RSB0_85") (pintype "bidirectional"))
      (node (ref "R65") (pin "1") (pinfunction "1_1") (pintype "passive"))
      (node (ref "U$10") (pin "P$8") (pinfunction "A6_P$8") (pintype "bidirectional"))
    )
    (net (code "136") (name "CH8_TIA") (class "Default")
      (node (ref "CH8") (pin "P3") (pinfunction "P3_P3") (pintype "bidirectional"))
      (node (ref "HCH8") (pin "12") (pinfunction "12_12") (pintype "passive"))
      (node (ref "U$6") (pin "P$14") (pinfunction "B1_P$14") (pintype "bidirectional"))
    )
    (net (code "137") (name "CH8_TIB") (class "Default")
      (node (ref "CH8") (pin "P5") (pinfunction "P5_P5") (pintype "bidirectional"))
      (node (ref "HCH8") (pin "8") (pinfunction "8_8") (pintype "passive"))
      (node (ref "U$6") (pin "P$12") (pinfunction "B3_P$12") (pintype "bidirectional"))
    )
    (net (code "138") (name "CH8_TIC") (class "Default")
      (node (ref "CH8") (pin "P7") (pinfunction "P7_P7") (pintype "bidirectional"))
      (node (ref "HCH8") (pin "4") (pinfunction "4_4") (pintype "passive"))
      (node (ref "U$6") (pin "P$10") (pinfunction "B5_P$10") (pintype "bidirectional"))
    )
    (net (code "139") (name "CH8_TOA") (class "Default")
      (node (ref "CH8") (pin "P4") (pinfunction "P4_P4") (pintype "bidirectional"))
      (node (ref "HCH8") (pin "10") (pinfunction "10_10") (pintype "passive"))
      (node (ref "U$6") (pin "P$13") (pinfunction "B2_P$13") (pintype "bidirectional"))
    )
    (net (code "140") (name "CH8_TOB") (class "Default")
      (node (ref "CH8") (pin "P6") (pinfunction "P6_P6") (pintype "bidirectional"))
      (node (ref "HCH8") (pin "6") (pinfunction "6_6") (pintype "passive"))
      (node (ref "U$6") (pin "P$11") (pinfunction "B4_P$11") (pintype "bidirectional"))
    )
    (net (code "141") (name "CH8_TOC") (class "Default")
      (node (ref "CH8") (pin "P8") (pinfunction "P8_P8") (pintype "bidirectional"))
      (node (ref "HCH8") (pin "2") (pinfunction "2_2") (pintype "passive"))
      (node (ref "U$6") (pin "P$9") (pinfunction "B6_P$9") (pintype "bidirectional"))
    )
    (net (code "142") (name "CLK") (class "Default")
      (node (ref "IC1") (pin "43") (pinfunction "P1[27]/CLKOUT/USB_OVRCR/CAP0[1]_43") (pintype "bidirectional"))
      (node (ref "IC2") (pin "11") (pinfunction "GFB0/IO123RSB1_11") (pintype "bidirectional"))
      (node (ref "TP3") (pin "TP") (pinfunction "TP_TP") (pintype "input"))
    )
    (net (code "143") (name "D-") (class "Default")
      (node (ref "C15") (pin "1") (pinfunction "1_1") (pintype "passive"))
      (node (ref "R18") (pin "2") (pinfunction "2_2") (pintype "passive"))
      (node (ref "X1") (pin "D+") (pinfunction "D+_D+") (pintype "bidirectional"))
    )
    (net (code "144") (name "DATA0") (class "Default")
      (node (ref "IC1") (pin "87") (pinfunction "P1[16]/ENET_MDC_87") (pintype "bidirectional"))
      (node (ref "IC2") (pin "23") (pinfunction "GEA0/IO107RSB1_23") (pintype "bidirectional"))
    )
    (net (code "145") (name "DATA1") (class "Default")
      (node (ref "IC1") (pin "86") (pinfunction "P1[17]/ENET_MDIO_86") (pintype "bidirectional"))
      (node (ref "IC2") (pin "22") (pinfunction "GEA1/IO108RSB1_22") (pintype "bidirectional"))
    )
    (net (code "146") (name "DATA2") (class "Default")
      (node (ref "IC1") (pin "32") (pinfunction "P1[18]/USB_UP_LED/PWM1[1]/CAP1[0]_32") (pintype "bidirectional"))
      (node (ref "IC2") (pin "21") (pinfunction "GEB0/IO109RSB1_21") (pintype "bidirectional"))
    )
    (net (code "147") (name "DATA3") (class "Default")
      (node (ref "IC1") (pin "33") (pinfunction "P1[19]/MCOA0/USB_PPWR/CAP1[1]_33") (pintype "bidirectional"))
      (node (ref "IC2") (pin "20") (pinfunction "GEB1/IO110RSB1_20") (pintype "bidirectional"))
    )
    (net (code "148") (name "DATA4") (class "Default")
      (node (ref "IC1") (pin "34") (pinfunction "P1[20]/MCI0/PWM1[2]/SCK0_34") (pintype "bidirectional"))
      (node (ref "IC2") (pin "19") (pinfunction "GEC0/IO111RSB1_19") (pintype "bidirectional"))
    )
    (net (code "149") (name "DATA5") (class "Default")
      (node (ref "IC1") (pin "35") (pinfunction "P1[21]/MCABORT/PWM1[3]/SSEL0_35") (pintype "bidirectional"))
      (node (ref "IC2") (pin "16") (pinfunction "GFA2/IO120RSB1_16") (pintype "bidirectional"))
    )
    (net (code "150") (name "DATA6") (class "Default")
      (node (ref "IC1") (pin "36") (pinfunction "P1[22]/MCOB0/USB_PWRD/MAT1[0]_36") (pintype "bidirectional"))
      (node (ref "IC2") (pin "15") (pinfunction "GFA1/IO121RSB1_15") (pintype "bidirectional"))
    )
    (net (code "151") (name "DATA7") (class "Default")
      (node (ref "IC1") (pin "37") (pinfunction "P1[23]/MCI1/PWM1[4]/MISO0_37") (pintype "bidirectional"))
      (node (ref "IC2") (pin "13") (pinfunction "GFA0/IO122RSB1_13") (pintype "bidirectional"))
    )
    (net (code "152") (name "DATA8") (class "Default")
      (node (ref "IC1") (pin "75") (pinfunction "P2[0]/PWM1[1]/TXD1_75") (pintype "bidirectional"))
      (node (ref "IC2") (pin "3") (pinfunction "IO68RSB1_3") (pintype "bidirectional"))
    )
    (net (code "153") (name "DATA9") (class "Default")
      (node (ref "IC1") (pin "74") (pinfunction "P2[1]/PWM1[2]/RXD1_74") (pintype "bidirectional"))
      (node (ref "IC2") (pin "2") (pinfunction "GAA2/IO67RSB3_2") (pintype "bidirectional"))
    )
    (net (code "154") (name "DATA10") (class "Default")
      (node (ref "IC1") (pin "73") (pinfunction "P2[2]/PWM1[3]/CTS1/TRACEDATA[3]_73") (pintype "bidirectional"))
      (node (ref "IC2") (pin "95") (pinfunction "GAC1/IO05RSB0_95") (pintype "bidirectional"))
    )
    (net (code "155") (name "DATA11") (class "Default")
      (node (ref "IC1") (pin "70") (pinfunction "P2[3]/PWM1[4]/DCD1/TRACEDATA[2]_70") (pintype "bidirectional"))
      (node (ref "IC2") (pin "96") (pinfunction "GAC0/IO04RSB0_96") (pintype "bidirectional"))
    )
    (net (code "156") (name "DATA12") (class "Default")
      (node (ref "IC1") (pin "69") (pinfunction "P2[4]/PWM1[5]/DSR1/TRACEDATA[1]_69") (pintype "bidirectional"))
      (node (ref "IC2") (pin "97") (pinfunction "GAB1/IO03RSB0_97") (pintype "bidirectional"))
    )
    (net (code "157") (name "DATA13") (class "Default")
      (node (ref "IC1") (pin "68") (pinfunction "P2[5]/PWM1[6]/DTR1/TRACEDATA[0]_68") (pintype "bidirectional"))
      (node (ref "IC2") (pin "98") (pinfunction "GAB0/IO02RSB0_98") (pintype "bidirectional"))
    )
    (net (code "158") (name "DATA14") (class "Default")
      (node (ref "IC1") (pin "67") (pinfunction "P2[6]/PCAP1[0]/RI1/TRACECLK_67") (pintype "bidirectional"))
      (node (ref "IC2") (pin "99") (pinfunction "GAA1/IO01RSB0_99") (pintype "bidirectional"))
    )
    (net (code "159") (name "DATA15") (class "Default")
      (node (ref "IC1") (pin "66") (pinfunction "P2[7]/RD2/RTS1_66") (pintype "bidirectional"))
      (node (ref "IC2") (pin "100") (pinfunction "GAA0/IO00RSB0_100") (pintype "bidirectional"))
    )
    (net (code "160") (name "EN_CORE") (class "Default")
      (node (ref "IC1") (pin "60") (pinfunction "P0[18]/DCD1/MOSI0/MOSI_60") (pintype "bidirectional"))
      (node (ref "LM3671") (pin "3") (pinfunction "EN_3") (pintype "bidirectional"))
    )
    (net (code "161") (name "EN_IO") (class "Default")
      (node (ref "IC1") (pin "61") (pinfunction "P0[17]/CTS1/MISO0/MISO_61") (pintype "bidirectional"))
      (node (ref "LM1") (pin "3") (pinfunction "EN_3") (pintype "bidirectional"))
    )
    (net (code "162") (name "F_TCK") (class "Default")
      (node (ref "IC1") (pin "95") (pinfunction "P1[0]/ENET_TXD0_95") (pintype "bidirectional"))
      (node (ref "IC2") (pin "47") (pinfunction "TCK_47") (pintype "bidirectional"))
      (node (ref "JTAG_A3PN") (pin "1") (pinfunction "1_1") (pintype "passive"))
      (node (ref "R83") (pin "2") (pinfunction "2_2") (pintype "passive"))
    )
    (net (code "163") (name "F_TDI") (class "Default")
      (node (ref "IC1") (pin "92") (pinfunction "P1[8]/ENET_CRS_92") (pintype "bidirectional"))
      (node (ref "IC2") (pin "48") (pinfunction "TDI_48") (pintype "bidirectional"))
      (node (ref "JTAG_A3PN") (pin "9") (pinfunction "9_9") (pintype "passive"))
    )
    (net (code "164") (name "F_TDO") (class "Default")
      (node (ref "IC1") (pin "94") (pinfunction "P1[1]/ENET_TXD1_94") (pintype "bidirectional"))
      (node (ref "IC2") (pin "54") (pinfunction "TDO_54") (pintype "bidirectional"))
      (node (ref "JTAG_A3PN") (pin "3") (pinfunction "3_3") (pintype "passive"))
    )
    (net (code "165") (name "F_TMS") (class "Default")
      (node (ref "IC1") (pin "93") (pinfunction "P1[4]/ENET_TX_EN_93") (pintype "bidirectional"))
      (node (ref "IC2") (pin "49") (pinfunction "TMS_49") (pintype "bidirectional"))
      (node (ref "JTAG_A3PN") (pin "5") (pinfunction "5_5") (pintype "passive"))
    )
    (net (code "166") (name "F_TRST") (class "Default")
      (node (ref "IC1") (pin "91") (pinfunction "P1[9]/ENET_RXD0_91") (pintype "bidirectional"))
      (node (ref "IC2") (pin "55") (pinfunction "TRST_55") (pintype "bidirectional"))
      (node (ref "JTAG_A3PN") (pin "8") (pinfunction "8_8") (pintype "passive"))
      (node (ref "R84") (pin "2") (pinfunction "2_2") (pintype "passive"))
    )
    (net (code "167") (name "GND") (class "Default")
      (node (ref "C1") (pin "-") (pinfunction "-_-") (pintype "passive"))
      (node (ref "C10") (pin "1") (pinfunction "1_1") (pintype "passive"))
      (node (ref "C11") (pin "1") (pinfunction "1_1") (pintype "passive"))
      (node (ref "C12") (pin "1") (pinfunction "1_1") (pintype "passive"))
      (node (ref "C13") (pin "1") (pinfunction "1_1") (pintype "passive"))
      (node (ref "C14") (pin "2") (pinfunction "2_2") (pintype "passive"))
      (node (ref "C15") (pin "2") (pinfunction "2_2") (pintype "passive"))
      (node (ref "C16") (pin "1") (pinfunction "1_1") (pintype "passive"))
      (node (ref "C17") (pin "1") (pinfunction "1_1") (pintype "passive"))
      (node (ref "C18") (pin "2") (pinfunction "2_2") (pintype "passive"))
      (node (ref "C19") (pin "-") (pinfunction "-_-") (pintype "passive"))
      (node (ref "C2") (pin "-") (pinfunction "-_-") (pintype "passive"))
      (node (ref "C20") (pin "2") (pinfunction "2_2") (pintype "passive"))
      (node (ref "C21") (pin "2") (pinfunction "2_2") (pintype "passive"))
      (node (ref "C22") (pin "2") (pinfunction "2_2") (pintype "passive"))
      (node (ref "C23") (pin "2") (pinfunction "2_2") (pintype "passive"))
      (node (ref "C24") (pin "2") (pinfunction "2_2") (pintype "passive"))
      (node (ref "C25") (pin "2") (pinfunction "2_2") (pintype "passive"))
      (node (ref "C26") (pin "2") (pinfunction "2_2") (pintype "passive"))
      (node (ref "C27") (pin "2") (pinfunction "2_2") (pintype "passive"))
      (node (ref "C28") (pin "1") (pinfunction "1_1") (pintype "passive"))
      (node (ref "C29") (pin "1") (pinfunction "1_1") (pintype "passive"))
      (node (ref "C3") (pin "2") (pinfunction "2_2") (pintype "passive"))
      (node (ref "C30") (pin "2") (pinfunction "2_2") (pintype "passive"))
      (node (ref "C31") (pin "-") (pinfunction "-_-") (pintype "passive"))
      (node (ref "C32") (pin "-") (pinfunction "-_-") (pintype "passive"))
      (node (ref "C33") (pin "2") (pinfunction "2_2") (pintype "passive"))
      (node (ref "C34") (pin "-") (pinfunction "-_-") (pintype "passive"))
      (node (ref "C35") (pin "-") (pinfunction "-_-") (pintype "passive"))
      (node (ref "C36") (pin "-") (pinfunction "-_-") (pintype "passive"))
      (node (ref "C37") (pin "2") (pinfunction "2_2") (pintype "passive"))
      (node (ref "C38") (pin "1") (pinfunction "1_1") (pintype "passive"))
      (node (ref "C39") (pin "1") (pinfunction "1_1") (pintype "passive"))
      (node (ref "C4") (pin "2") (pinfunction "2_2") (pintype "passive"))
      (node (ref "C40") (pin "1") (pinfunction "1_1") (pintype "passive"))
      (node (ref "C41") (pin "1") (pinfunction "1_1") (pintype "passive"))
      (node (ref "C42") (pin "1") (pinfunction "1_1") (pintype "passive"))
      (node (ref "C43") (pin "1") (pinfunction "1_1") (pintype "passive"))
      (node (ref "C44") (pin "1") (pinfunction "1_1") (pintype "passive"))
      (node (ref "C45") (pin "1") (pinfunction "1_1") (pintype "passive"))
      (node (ref "C46") (pin "1") (pinfunction "1_1") (pintype "passive"))
      (node (ref "C47") (pin "1") (pinfunction "1_1") (pintype "passive"))
      (node (ref "C48") (pin "1") (pinfunction "1_1") (pintype "passive"))
      (node (ref "C49") (pin "1") (pinfunction "1_1") (pintype "passive"))
      (node (ref "C5") (pin "1") (pinfunction "1_1") (pintype "passive"))
      (node (ref "C50") (pin "1") (pinfunction "1_1") (pintype "passive"))
      (node (ref "C51") (pin "-") (pinfunction "-_-") (pintype "passive"))
      (node (ref "C52") (pin "-") (pinfunction "-_-") (pintype "passive"))
      (node (ref "C53") (pin "-") (pinfunction "-_-") (pintype "passive"))
      (node (ref "C54") (pin "-") (pinfunction "-_-") (pintype "passive"))
      (node (ref "C55") (pin "-") (pinfunction "-_-") (pintype "passive"))
      (node (ref "C56") (pin "-") (pinfunction "-_-") (pintype "passive"))
      (node (ref "C57") (pin "-") (pinfunction "-_-") (pintype "passive"))
      (node (ref "C6") (pin "1") (pinfunction "1_1") (pintype "passive"))
      (node (ref "C7") (pin "1") (pinfunction "1_1") (pintype "passive"))
      (node (ref "C8") (pin "1") (pinfunction "1_1") (pintype "passive"))
      (node (ref "C9") (pin "1") (pinfunction "1_1") (pintype "passive"))
      (node (ref "CH1") (pin "P1") (pinfunction "P1_P1") (pintype "bidirectional"))
      (node (ref "CH2") (pin "P1") (pinfunction "P1_P1") (pintype "bidirectional"))
      (node (ref "CH3") (pin "P1") (pinfunction "P1_P1") (pintype "bidirectional"))
      (node (ref "CH4") (pin "P1") (pinfunction "P1_P1") (pintype "bidirectional"))
      (node (ref "CH5") (pin "P1") (pinfunction "P1_P1") (pintype "bidirectional"))
      (node (ref "CH6") (pin "P1") (pinfunction "P1_P1") (pintype "bidirectional"))
      (node (ref "CH7") (pin "P1") (pinfunction "P1_P1") (pintype "bidirectional"))
      (node (ref "CH8") (pin "P1") (pinfunction "P1_P1") (pintype "bidirectional"))
      (node (ref "FT230X") (pin "13") (pinfunction "GND2_13") (pintype "power_in"))
      (node (ref "FT230X") (pin "3") (pinfunction "GND1_3") (pintype "power_in"))
      (node (ref "FT230X") (pin "C") (pinfunction "GND3_C") (pintype "power_in"))
      (node (ref "HCH1") (pin "13") (pinfunction "13_13") (pintype "passive"))
      (node (ref "HCH2") (pin "13") (pinfunction "13_13") (pintype "passive"))
      (node (ref "HCH3") (pin "13") (pinfunction "13_13") (pintype "passive"))
      (node (ref "HCH4") (pin "13") (pinfunction "13_13") (pintype "passive"))
      (node (ref "HCH5") (pin "13") (pinfunction "13_13") (pintype "passive"))
      (node (ref "HCH6") (pin "13") (pinfunction "13_13") (pintype "passive"))
      (node (ref "HCH7") (pin "13") (pinfunction "13_13") (pintype "passive"))
      (node (ref "HCH8") (pin "13") (pinfunction "13_13") (pintype "passive"))
      (node (ref "IC1") (pin "11") (pinfunction "VSSA_11") (pintype "bidirectional"))
      (node (ref "IC1") (pin "15") (pinfunction "VREFN_15") (pintype "bidirectional"))
      (node (ref "IC1") (pin "31") (pinfunction "VSS1_31") (pintype "bidirectional"))
      (node (ref "IC1") (pin "41") (pinfunction "VSS2_41") (pintype "bidirectional"))
      (node (ref "IC1") (pin "55") (pinfunction "VSS3_55") (pintype "bidirectional"))
      (node (ref "IC1") (pin "72") (pinfunction "VSS4_72") (pintype "bidirectional"))
      (node (ref "IC1") (pin "83") (pinfunction "VSS6_83") (pintype "bidirectional"))
      (node (ref "IC1") (pin "97") (pinfunction "VSS5_97") (pintype "bidirectional"))
      (node (ref "IC2") (pin "1") (pinfunction "GND_1") (pintype "power_in"))
      (node (ref "IC2") (pin "12") (pinfunction "VCOMPLF_12") (pintype "power_in"))
      (node (ref "IC2") (pin "25") (pinfunction "GNDQ_25") (pintype "power_in"))
      (node (ref "IC2") (pin "38") (pinfunction "GND_38") (pintype "power_in"))
      (node (ref "IC2") (pin "51") (pinfunction "GND_51") (pintype "power_in"))
      (node (ref "IC2") (pin "67") (pinfunction "GND_67") (pintype "power_in"))
      (node (ref "IC2") (pin "75") (pinfunction "GNDQ_75") (pintype "power_in"))
      (node (ref "IC2") (pin "88") (pinfunction "GND_88") (pintype "power_in"))
      (node (ref "IC2") (pin "9") (pinfunction "GND_9") (pintype "power_in"))
      (node (ref "ISP") (pin "P$1") (pinfunction "0_P$1") (pintype "passive"))
      (node (ref "JP1") (pin "1") (pinfunction "1_1") (pintype "passive"))
      (node (ref "JP2") (pin "1") (pinfunction "1_1") (pintype "passive"))
      (node (ref "JP3") (pin "1") (pinfunction "1_1") (pintype "passive"))
      (node (ref "JP4") (pin "1") (pinfunction "1_1") (pintype "passive"))
      (node (ref "JTAG_A3PN") (pin "10") (pinfunction "10_10") (pintype "passive"))
      (node (ref "JTAG_A3PN") (pin "2") (pinfunction "2_2") (pintype "passive"))
      (node (ref "JTAG_LPC") (pin "10") (pinfunction "10_10") (pintype "passive"))
      (node (ref "JTAG_LPC") (pin "12") (pinfunction "12_12") (pintype "passive"))
      (node (ref "JTAG_LPC") (pin "14") (pinfunction "14_14") (pintype "passive"))
      (node (ref "JTAG_LPC") (pin "16") (pinfunction "16_16") (pintype "passive"))
      (node (ref "JTAG_LPC") (pin "18") (pinfunction "18_18") (pintype "passive"))
      (node (ref "JTAG_LPC") (pin "20") (pinfunction "20_20") (pintype "passive"))
      (node (ref "JTAG_LPC") (pin "4") (pinfunction "4_4") (pintype "passive"))
      (node (ref "JTAG_LPC") (pin "6") (pinfunction "6_6") (pintype "passive"))
      (node (ref "JTAG_LPC") (pin "8") (pinfunction "8_8") (pintype "passive"))
      (node (ref "LM1") (pin "2") (pinfunction "GND_2") (pintype "bidirectional"))
      (node (ref "LM2") (pin "2") (pinfunction "GND_2") (pintype "bidirectional"))
      (node (ref "LM3671") (pin "2") (pinfunction "GND_2") (pintype "bidirectional"))
      (node (ref "PWR_UP") (pin "C") (pinfunction "C_C") (pintype "passive"))
      (node (ref "R10") (pin "1") (pinfunction "1_1") (pintype "passive"))
      (node (ref "R14") (pin "1") (pinfunction "1_1") (pintype "passive"))
      (node (ref "R15") (pin "1") (pinfunction "1_1") (pintype "passive"))
      (node (ref "R83") (pin "1") (pinfunction "1_1") (pintype "passive"))
      (node (ref "R84") (pin "1") (pinfunction "1_1") (pintype "passive"))
      (node (ref "RESET") (pin "P$1") (pinfunction "0_P$1") (pintype "passive"))
      (node (ref "TP7") (pin "TP") (pinfunction "TP_TP") (pintype "input"))
      (node (ref "TP8") (pin "TP") (pinfunction "TP_TP") (pintype "input"))
      (node (ref "TP9") (pin "TP") (pinfunction "TP_TP") (pintype "input"))
      (node (ref "U$10") (pin "P$1") (pinfunction "GND_P$1") (pintype "power_in"))
      (node (ref "U$11") (pin "P$1") (pinfunction "P$1_P$1") (pintype "power_in"))
      (node (ref "U$12") (pin "P$1") (pinfunction "P$1_P$1") (pintype "power_in"))
      (node (ref "U$13") (pin "P$1") (pinfunction "P$1_P$1") (pintype "power_in"))
      (node (ref "U$14") (pin "P$1") (pinfunction "P$1_P$1") (pintype "power_in"))
      (node (ref "U$15") (pin "P$1") (pinfunction "P$1_P$1") (pintype "power_in"))
      (node (ref "U$16") (pin "P$1") (pinfunction "P$1_P$1") (pintype "power_in"))
      (node (ref "U$17") (pin "P$1") (pinfunction "P$1_P$1") (pintype "power_in"))
      (node (ref "U$18") (pin "P$1") (pinfunction "P$1_P$1") (pintype "power_in"))
      (node (ref "U$3") (pin "P$1") (pinfunction "GND_P$1") (pintype "power_in"))
      (node (ref "U$4") (pin "P$1") (pinfunction "GND_P$1") (pintype "power_in"))
      (node (ref "U$5") (pin "P$1") (pinfunction "GND_P$1") (pintype "power_in"))
      (node (ref "U$6") (pin "P$1") (pinfunction "GND_P$1") (pintype "power_in"))
      (node (ref "U$7") (pin "P$1") (pinfunction "GND_P$1") (pintype "power_in"))
      (node (ref "U$8") (pin "P$1") (pinfunction "GND_P$1") (pintype "power_in"))
      (node (ref "U$9") (pin "P$1") (pinfunction "GND_P$1") (pintype "power_in"))
      (node (ref "X1") (pin "GND") (pinfunction "GND_GND") (pintype "bidirectional"))
    )
    (net (code "168") (name "LED1") (class "Default")
      (node (ref "IC1") (pin "76") (pinfunction "P0[9]/I2STX_SDA/MOSI1/MAT2[3]_76") (pintype "bidirectional"))
      (node (ref "R4") (pin "1") (pinfunction "1_1") (pintype "passive"))
    )
    (net (code "169") (name "LED2") (class "Default")
      (node (ref "IC1") (pin "77") (pinfunction "P0[8]/I2STX_WS/MISO1/MAT2[2]_77") (pintype "bidirectional"))
      (node (ref "R5") (pin "1") (pinfunction "1_1") (pintype "passive"))
    )
    (net (code "170") (name "LED3") (class "Default")
      (node (ref "IC1") (pin "78") (pinfunction "P0[7]/I2STX_CLK/SCK1/MAT2[1]_78") (pintype "bidirectional"))
      (node (ref "R6") (pin "1") (pinfunction "1_1") (pintype "passive"))
    )
    (net (code "171") (name "LED4") (class "Default")
      (node (ref "IC1") (pin "79") (pinfunction "P0[6]/I2SRX_SDA/SSEL1/MAT2[0]_79") (pintype "bidirectional"))
      (node (ref "R7") (pin "1") (pinfunction "1_1") (pintype "passive"))
    )
    (net (code "172") (name "Net-(C14-Pad1)") (class "Default")
      (node (ref "C14") (pin "1") (pinfunction "1_1") (pintype "passive"))
      (node (ref "R17") (pin "2") (pinfunction "2_2") (pintype "passive"))
      (node (ref "X1") (pin "D-") (pinfunction "D-_D-") (pintype "bidirectional"))
    )
    (net (code "173") (name "Net-(FT230X-3V3OUT)") (class "Default")
      (node (ref "C16") (pin "2") (pinfunction "2_2") (pintype "passive"))
      (node (ref "FT230X") (pin "1") (pinfunction "VCCIO_1") (pintype "input"))
      (node (ref "FT230X") (pin "8") (pinfunction "3V3OUT_8") (pintype "output"))
      (node (ref "FT230X") (pin "9") (pinfunction "RESET#_9") (pintype "input"))
    )
    (net (code "174") (name "Net-(FT230X-USBDM)") (class "Default")
      (node (ref "FT230X") (pin "7") (pinfunction "USBDM_7") (pintype "bidirectional"))
      (node (ref "R17") (pin "1") (pinfunction "1_1") (pintype "passive"))
    )
    (net (code "175") (name "Net-(FT230X-USBDP)") (class "Default")
      (node (ref "FT230X") (pin "6") (pinfunction "USBDP_6") (pintype "bidirectional"))
      (node (ref "R18") (pin "1") (pinfunction "1_1") (pintype "passive"))
    )
    (net (code "176") (name "Net-(IC1-XTAL1)") (class "Default")
      (node (ref "C4") (pin "1") (pinfunction "1_1") (pintype "passive"))
      (node (ref "IC1") (pin "22") (pinfunction "XTAL1_22") (pintype "bidirectional"))
      (node (ref "Q1") (pin "1") (pinfunction "1_1") (pintype "passive"))
    )
    (net (code "177") (name "Net-(IC1-XTAL2)") (class "Default")
      (node (ref "C3") (pin "1") (pinfunction "1_1") (pintype "passive"))
      (node (ref "IC1") (pin "23") (pinfunction "XTAL2_23") (pintype "bidirectional"))
      (node (ref "Q1") (pin "3") (pinfunction "2_3") (pintype "passive"))
    )
    (net (code "178") (name "Net-(JTAG_LPC-Pad17)") (class "Default")
      (node (ref "JTAG_LPC") (pin "17") (pinfunction "17_17") (pintype "passive"))
      (node (ref "R10") (pin "2") (pinfunction "2_2") (pintype "passive"))
    )
    (net (code "179") (name "Net-(L2-1)") (class "Default")
      (node (ref "L2") (pin "P$1") (pinfunction "1_P$1") (pintype "passive"))
      (node (ref "LM3671") (pin "5") (pinfunction "SW_5") (pintype "bidirectional"))
    )
    (net (code "180") (name "Net-(L3-1)") (class "Default")
      (node (ref "L3") (pin "P$1") (pinfunction "1_P$1") (pintype "passive"))
      (node (ref "LM1") (pin "5") (pinfunction "SW_5") (pintype "bidirectional"))
    )
    (net (code "181") (name "Net-(L4-1)") (class "Default")
      (node (ref "L4") (pin "P$1") (pinfunction "1_P$1") (pintype "passive"))
      (node (ref "LM2") (pin "5") (pinfunction "SW_5") (pintype "bidirectional"))
    )
    (net (code "182") (name "Net-(LED1-PadC)") (class "Default")
      (node (ref "LED1") (pin "C") (pinfunction "C_C") (pintype "passive"))
      (node (ref "R4") (pin "2") (pinfunction "2_2") (pintype "passive"))
    )
    (net (code "183") (name "Net-(LED2-PadC)") (class "Default")
      (node (ref "LED2") (pin "C") (pinfunction "C_C") (pintype "passive"))
      (node (ref "R5") (pin "2") (pinfunction "2_2") (pintype "passive"))
    )
    (net (code "184") (name "Net-(LED3-PadC)") (class "Default")
      (node (ref "LED3") (pin "C") (pinfunction "C_C") (pintype "passive"))
      (node (ref "R6") (pin "2") (pinfunction "2_2") (pintype "passive"))
    )
    (net (code "185") (name "Net-(LED4-PadC)") (class "Default")
      (node (ref "LED4") (pin "C") (pinfunction "C_C") (pintype "passive"))
      (node (ref "R7") (pin "2") (pinfunction "2_2") (pintype "passive"))
    )
    (net (code "186") (name "Net-(PWR_UP-PadA)") (class "Default")
      (node (ref "PWR_UP") (pin "A") (pinfunction "A_A") (pintype "passive"))
      (node (ref "R16") (pin "1") (pinfunction "1_1") (pintype "passive"))
    )
    (net (code "187") (name "RTCK") (class "Default")
      (node (ref "IC1") (pin "100") (pinfunction "RTCK_100") (pintype "bidirectional"))
      (node (ref "JTAG_LPC") (pin "11") (pinfunction "11_11") (pintype "passive"))
      (node (ref "R15") (pin "2") (pinfunction "2_2") (pintype "passive"))
    )
    (net (code "188") (name "RX0") (class "Default")
      (node (ref "FT230X") (pin "15") (pinfunction "TXD_15") (pintype "output"))
      (node (ref "IC1") (pin "99") (pinfunction "P0[3]/RXD0/AD0[6]_99") (pintype "bidirectional"))
      (node (ref "TP2") (pin "TP") (pinfunction "TP_TP") (pintype "input"))
    )
    (net (code "189") (name "RX1") (class "Default")
      (node (ref "IC1") (pin "63") (pinfunction "P0[16]/RXD1/SSEL0/SSEL_63") (pintype "bidirectional"))
      (node (ref "IC2") (pin "5") (pinfunction "IO132RSB1_5") (pintype "bidirectional"))
    )
    (net (code "190") (name "RX2") (class "Default")
      (node (ref "IC1") (pin "49") (pinfunction "P0[11]/RXD2/SCL2/MAT3[1]_49") (pintype "bidirectional"))
      (node (ref "IC2") (pin "6") (pinfunction "GAC2/IO131RSB1_6") (pintype "bidirectional"))
    )
    (net (code "191") (name "RX3") (class "Default")
      (node (ref "IC1") (pin "47") (pinfunction "P0[1]/TD1/RXD3/SCL1_47") (pintype "bidirectional"))
      (node (ref "IC2") (pin "8") (pinfunction "IO129RSB1_8") (pintype "bidirectional"))
    )
    (net (code "192") (name "TCK{slash}SWDCLK") (class "Default")
      (node (ref "IC1") (pin "5") (pinfunction "TCK/SWDCLK_5") (pintype "bidirectional"))
      (node (ref "JTAG_LPC") (pin "9") (pinfunction "9_9") (pintype "passive"))
      (node (ref "R14") (pin "2") (pinfunction "2_2") (pintype "passive"))
    )
    (net (code "193") (name "TDI") (class "Default")
      (node (ref "IC1") (pin "2") (pinfunction "TDI_2") (pintype "bidirectional"))
      (node (ref "JTAG_LPC") (pin "5") (pinfunction "5_5") (pintype "passive"))
      (node (ref "R11") (pin "1") (pinfunction "1_1") (pintype "passive"))
    )
    (net (code "194") (name "TDO{slash}SWO") (class "Default")
      (node (ref "IC1") (pin "1") (pinfunction "TDO/SWO_1") (pintype "bidirectional"))
      (node (ref "JTAG_LPC") (pin "13") (pinfunction "13_13") (pintype "passive"))
      (node (ref "R12") (pin "1") (pinfunction "1_1") (pintype "passive"))
    )
    (net (code "195") (name "TMS{slash}SWDIO") (class "Default")
      (node (ref "IC1") (pin "3") (pinfunction "TMS/SWDIO_3") (pintype "bidirectional"))
      (node (ref "JTAG_LPC") (pin "7") (pinfunction "7_7") (pintype "passive"))
      (node (ref "R13") (pin "1") (pinfunction "1_1") (pintype "passive"))
    )
    (net (code "196") (name "TRST") (class "Default")
      (node (ref "IC1") (pin "4") (pinfunction "TRST_4") (pintype "bidirectional"))
      (node (ref "JTAG_LPC") (pin "3") (pinfunction "3_3") (pintype "passive"))
    )
    (net (code "197") (name "TX0") (class "Default")
      (node (ref "FT230X") (pin "2") (pinfunction "RXD_2") (pintype "input"))
      (node (ref "IC1") (pin "98") (pinfunction "P0[2]/TXD0/AD0[7]_98") (pintype "bidirectional"))
      (node (ref "TP1") (pin "TP") (pinfunction "TP_TP") (pintype "input"))
    )
    (net (code "198") (name "TX1") (class "Default")
      (node (ref "IC1") (pin "62") (pinfunction "P0[15]/TXD1/SCK0/SCK_62") (pintype "bidirectional"))
      (node (ref "IC2") (pin "4") (pinfunction "GAB2/IO69RSB1_4") (pintype "bidirectional"))
    )
    (net (code "199") (name "TX2") (class "Default")
      (node (ref "IC1") (pin "48") (pinfunction "P0[10]/TXD2/SDA2/MAT3[0]_48") (pintype "bidirectional"))
      (node (ref "IC2") (pin "7") (pinfunction "IO130RSB1_7") (pintype "bidirectional"))
    )
    (net (code "200") (name "TX3") (class "Default")
      (node (ref "IC1") (pin "46") (pinfunction "P0[0]/RD1/TXD3/SDA1_46") (pintype "bidirectional"))
      (node (ref "IC2") (pin "10") (pinfunction "GFB1/IO124RSB1_10") (pintype "bidirectional"))
    )
    (net (code "201") (name "VA3CORE_1V5") (class "Default")
      (node (ref "C35") (pin "+") (pinfunction "+_+") (pintype "passive"))
      (node (ref "C37") (pin "1") (pinfunction "1_1") (pintype "passive"))
      (node (ref "C38") (pin "2") (pinfunction "2_2") (pintype "passive"))
      (node (ref "C39") (pin "2") (pinfunction "2_2") (pintype "passive"))
      (node (ref "C40") (pin "2") (pinfunction "2_2") (pintype "passive"))
      (node (ref "C41") (pin "2") (pinfunction "2_2") (pintype "passive"))
      (node (ref "C46") (pin "2") (pinfunction "2_2") (pintype "passive"))
      (node (ref "C50") (pin "2") (pinfunction "2_2") (pintype "passive"))
      (node (ref "IC2") (pin "14") (pinfunction "VCCPLF_14") (pintype "power_in"))
      (node (ref "IC2") (pin "17") (pinfunction "VCC_17") (pintype "power_in"))
      (node (ref "IC2") (pin "37") (pinfunction "VCC_37") (pintype "power_in"))
      (node (ref "IC2") (pin "68") (pinfunction "VCC_68") (pintype "power_in"))
      (node (ref "IC2") (pin "89") (pinfunction "VCC_89") (pintype "power_in"))
      (node (ref "L2") (pin "P$2") (pinfunction "2_P$2") (pintype "passive"))
      (node (ref "LM3671") (pin "4") (pinfunction "FB_4") (pintype "bidirectional"))
      (node (ref "TP5") (pin "TP") (pinfunction "TP_TP") (pintype "input"))
    )
    (net (code "202") (name "VA3IO_3V3") (class "Default")
      (node (ref "C1") (pin "+") (pinfunction "+_+") (pintype "passive"))
      (node (ref "C28") (pin "2") (pinfunction "2_2") (pintype "passive"))
      (node (ref "C29") (pin "2") (pinfunction "2_2") (pintype "passive"))
      (node (ref "C30") (pin "1") (pinfunction "1_1") (pintype "passive"))
      (node (ref "C42") (pin "2") (pinfunction "2_2") (pintype "passive"))
      (node (ref "C43") (pin "2") (pinfunction "2_2") (pintype "passive"))
      (node (ref "C44") (pin "2") (pinfunction "2_2") (pintype "passive"))
      (node (ref "C45") (pin "2") (pinfunction "2_2") (pintype "passive"))
      (node (ref "C47") (pin "2") (pinfunction "2_2") (pintype "passive"))
      (node (ref "C48") (pin "2") (pinfunction "2_2") (pintype "passive"))
      (node (ref "C49") (pin "2") (pinfunction "2_2") (pintype "passive"))
      (node (ref "IC2") (pin "18") (pinfunction "VCCIB1_18") (pintype "power_in"))
      (node (ref "IC2") (pin "24") (pinfunction "VMV1_24") (pintype "power_in"))
      (node (ref "IC2") (pin "39") (pinfunction "VCCIB1_39") (pintype "power_in"))
      (node (ref "IC2") (pin "50") (pinfunction "VMV1_50") (pintype "power_in"))
      (node (ref "IC2") (pin "52") (pinfunction "VPUMP_52") (pintype "power_in"))
      (node (ref "IC2") (pin "56") (pinfunction "VJTAG_56") (pintype "power_in"))
      (node (ref "IC2") (pin "66") (pinfunction "VCCIB0_66") (pintype "power_in"))
      (node (ref "IC2") (pin "74") (pinfunction "VMV0_74") (pintype "power_in"))
      (node (ref "IC2") (pin "87") (pinfunction "VCCIB0_87") (pintype "power_in"))
      (node (ref "JTAG_A3PN") (pin "6") (pinfunction "6_6") (pintype "passive"))
      (node (ref "JTAG_A3PN") (pin "7") (pinfunction "7_7") (pintype "passive"))
      (node (ref "L3") (pin "P$2") (pinfunction "2_P$2") (pintype "passive"))
      (node (ref "LM1") (pin "4") (pinfunction "FB_4") (pintype "bidirectional"))
      (node (ref "TP4") (pin "TP") (pinfunction "TP_TP") (pintype "input"))
    )
    (net (code "203") (name "VBUS1") (class "Default")
      (node (ref "C18") (pin "1") (pinfunction "1_1") (pintype "passive"))
      (node (ref "C19") (pin "+") (pinfunction "+_+") (pintype "passive"))
      (node (ref "FT230X") (pin "10") (pinfunction "VCC_10") (pintype "power_in"))
      (node (ref "L1") (pin "1") (pinfunction "2_1") (pintype "passive"))
    )
    (net (code "204") (name "VLPC_3V3") (class "Default")
      (node (ref "C10") (pin "2") (pinfunction "2_2") (pintype "passive"))
      (node (ref "C11") (pin "2") (pinfunction "2_2") (pintype "passive"))
      (node (ref "C12") (pin "2") (pinfunction "2_2") (pintype "passive"))
      (node (ref "C13") (pin "2") (pinfunction "2_2") (pintype "passive"))
      (node (ref "C31") (pin "+") (pinfunction "+_+") (pintype "passive"))
      (node (ref "C33") (pin "1") (pinfunction "1_1") (pintype "passive"))
      (node (ref "C36") (pin "+") (pinfunction "+_+") (pintype "passive"))
      (node (ref "C5") (pin "2") (pinfunction "2_2") (pintype "passive"))
      (node (ref "C6") (pin "2") (pinfunction "2_2") (pintype "passive"))
      (node (ref "C7") (pin "2") (pinfunction "2_2") (pintype "passive"))
      (node (ref "C8") (pin "2") (pinfunction "2_2") (pintype "passive"))
      (node (ref "C9") (pin "2") (pinfunction "2_2") (pintype "passive"))
      (node (ref "HCH1") (pin "14") (pinfunction "14_14") (pintype "passive"))
      (node (ref "HCH2") (pin "14") (pinfunction "14_14") (pintype "passive"))
      (node (ref "HCH3") (pin "14") (pinfunction "14_14") (pintype "passive"))
      (node (ref "HCH4") (pin "14") (pinfunction "14_14") (pintype "passive"))
      (node (ref "HCH5") (pin "14") (pinfunction "14_14") (pintype "passive"))
      (node (ref "HCH6") (pin "14") (pinfunction "14_14") (pintype "passive"))
      (node (ref "HCH7") (pin "14") (pinfunction "14_14") (pintype "passive"))
      (node (ref "HCH8") (pin "14") (pinfunction "14_14") (pintype "passive"))
      (node (ref "IC1") (pin "10") (pinfunction "VDDA_10") (pintype "bidirectional"))
      (node (ref "IC1") (pin "12") (pinfunction "VREFP_12") (pintype "bidirectional"))
      (node (ref "IC1") (pin "19") (pinfunction "VBAT_19") (pintype "bidirectional"))
      (node (ref "IC1") (pin "28") (pinfunction "VDD(3V3)1_28") (pintype "bidirectional"))
      (node (ref "IC1") (pin "42") (pinfunction "VDD(REG)(3V3)1_42") (pintype "bidirectional"))
      (node (ref "IC1") (pin "54") (pinfunction "VDD(3V3)2_54") (pintype "bidirectional"))
      (node (ref "IC1") (pin "71") (pinfunction "VDD(3V3)3_71") (pintype "bidirectional"))
      (node (ref "IC1") (pin "84") (pinfunction "VDD(REG)(3V3)2_84") (pintype "bidirectional"))
      (node (ref "IC1") (pin "96") (pinfunction "VDD(3V3)4_96") (pintype "bidirectional"))
      (node (ref "JTAG_LPC") (pin "1") (pinfunction "1_1") (pintype "passive"))
      (node (ref "JTAG_LPC") (pin "2") (pinfunction "2_2") (pintype "passive"))
      (node (ref "L4") (pin "P$2") (pinfunction "2_P$2") (pintype "passive"))
      (node (ref "LED1") (pin "A") (pinfunction "A_A") (pintype "passive"))
      (node (ref "LED2") (pin "A") (pinfunction "A_A") (pintype "passive"))
      (node (ref "LED3") (pin "A") (pinfunction "A_A") (pintype "passive"))
      (node (ref "LED4") (pin "A") (pinfunction "A_A") (pintype "passive"))
      (node (ref "LM2") (pin "4") (pinfunction "FB_4") (pintype "bidirectional"))
      (node (ref "LM3671") (pin "1") (pinfunction "VIN_1") (pintype "bidirectional"))
      (node (ref "R1") (pin "2") (pinfunction "2_2") (pintype "passive"))
      (node (ref "R11") (pin "2") (pinfunction "2_2") (pintype "passive"))
      (node (ref "R12") (pin "2") (pinfunction "2_2") (pintype "passive"))
      (node (ref "R13") (pin "2") (pinfunction "2_2") (pintype "passive"))
      (node (ref "R19") (pin "2") (pinfunction "2_2") (pintype "passive"))
      (node (ref "R2") (pin "2") (pinfunction "2_2") (pintype "passive"))
      (node (ref "R20") (pin "2") (pinfunction "2_2") (pintype "passive"))
      (node (ref "R21") (pin "2") (pinfunction "2_2") (pintype "passive"))
      (node (ref "R22") (pin "2") (pinfunction "2_2") (pintype "passive"))
      (node (ref "R23") (pin "2") (pinfunction "2_2") (pintype "passive"))
      (node (ref "R24") (pin "2") (pinfunction "2_2") (pintype "passive"))
      (node (ref "R25") (pin "2") (pinfunction "2_2") (pintype "passive"))
      (node (ref "R26") (pin "2") (pinfunction "2_2") (pintype "passive"))
      (node (ref "R27") (pin "2") (pinfunction "2_2") (pintype "passive"))
      (node (ref "R28") (pin "2") (pinfunction "2_2") (pintype "passive"))
      (node (ref "R29") (pin "2") (pinfunction "2_2") (pintype "passive"))
      (node (ref "R3") (pin "2") (pinfunction "2_2") (pintype "passive"))
      (node (ref "R30") (pin "2") (pinfunction "2_2") (pintype "passive"))
      (node (ref "R31") (pin "2") (pinfunction "2_2") (pintype "passive"))
      (node (ref "R32") (pin "2") (pinfunction "2_2") (pintype "passive"))
      (node (ref "R33") (pin "2") (pinfunction "2_2") (pintype "passive"))
      (node (ref "R34") (pin "2") (pinfunction "2_2") (pintype "passive"))
      (node (ref "R35") (pin "2") (pinfunction "2_2") (pintype "passive"))
      (node (ref "R36") (pin "2") (pinfunction "2_2") (pintype "passive"))
      (node (ref "R37") (pin "2") (pinfunction "2_2") (pintype "passive"))
      (node (ref "R38") (pin "2") (pinfunction "2_2") (pintype "passive"))
      (node (ref "R39") (pin "2") (pinfunction "2_2") (pintype "passive"))
      (node (ref "R40") (pin "2") (pinfunction "2_2") (pintype "passive"))
      (node (ref "R41") (pin "2") (pinfunction "2_2") (pintype "passive"))
      (node (ref "R42") (pin "2") (pinfunction "2_2") (pintype "passive"))
      (node (ref "R43") (pin "2") (pinfunction "2_2") (pintype "passive"))
      (node (ref "R44") (pin "2") (pinfunction "2_2") (pintype "passive"))
      (node (ref "R45") (pin "2") (pinfunction "2_2") (pintype "passive"))
      (node (ref "R46") (pin "2") (pinfunction "2_2") (pintype "passive"))
      (node (ref "R47") (pin "2") (pinfunction "2_2") (pintype "passive"))
      (node (ref "R48") (pin "2") (pinfunction "2_2") (pintype "passive"))
      (node (ref "R49") (pin "2") (pinfunction "2_2") (pintype "passive"))
      (node (ref "R50") (pin "2") (pinfunction "2_2") (pintype "passive"))
      (node (ref "R51") (pin "2") (pinfunction "2_2") (pintype "passive"))
      (node (ref "R52") (pin "2") (pinfunction "2_2") (pintype "passive"))
      (node (ref "R53") (pin "2") (pinfunction "2_2") (pintype "passive"))
      (node (ref "R54") (pin "2") (pinfunction "2_2") (pintype "passive"))
      (node (ref "R55") (pin "2") (pinfunction "2_2") (pintype "passive"))
      (node (ref "R56") (pin "2") (pinfunction "2_2") (pintype "passive"))
      (node (ref "R57") (pin "2") (pinfunction "2_2") (pintype "passive"))
      (node (ref "R58") (pin "2") (pinfunction "2_2") (pintype "passive"))
      (node (ref "R59") (pin "2") (pinfunction "2_2") (pintype "passive"))
      (node (ref "R60") (pin "2") (pinfunction "2_2") (pintype "passive"))
      (node (ref "R61") (pin "2") (pinfunction "2_2") (pintype "passive"))
      (node (ref "R62") (pin "2") (pinfunction "2_2") (pintype "passive"))
      (node (ref "R63") (pin "2") (pinfunction "2_2") (pintype "passive"))
      (node (ref "R64") (pin "2") (pinfunction "2_2") (pintype "passive"))
      (node (ref "R65") (pin "2") (pinfunction "2_2") (pintype "passive"))
      (node (ref "R66") (pin "2") (pinfunction "2_2") (pintype "passive"))
      (node (ref "R67") (pin "2") (pinfunction "2_2") (pintype "passive"))
      (node (ref "R68") (pin "2") (pinfunction "2_2") (pintype "passive"))
      (node (ref "R69") (pin "2") (pinfunction "2_2") (pintype "passive"))
      (node (ref "R70") (pin "2") (pinfunction "2_2") (pintype "passive"))
      (node (ref "R71") (pin "2") (pinfunction "2_2") (pintype "passive"))
      (node (ref "R8") (pin "2") (pinfunction "2_2") (pintype "passive"))
      (node (ref "R9") (pin "2") (pinfunction "2_2") (pintype "passive"))
      (node (ref "TP6") (pin "TP") (pinfunction "TP_TP") (pintype "input"))
      (node (ref "U$10") (pin "P$2") (pinfunction "VREFA_P$2") (pintype "power_in"))
      (node (ref "U$3") (pin "P$2") (pinfunction "VREFA_P$2") (pintype "power_in"))
      (node (ref "U$4") (pin "P$2") (pinfunction "VREFA_P$2") (pintype "power_in"))
      (node (ref "U$5") (pin "P$2") (pinfunction "VREFA_P$2") (pintype "power_in"))
      (node (ref "U$6") (pin "P$2") (pinfunction "VREFA_P$2") (pintype "power_in"))
      (node (ref "U$7") (pin "P$2") (pinfunction "VREFA_P$2") (pintype "power_in"))
      (node (ref "U$8") (pin "P$2") (pinfunction "VREFA_P$2") (pintype "power_in"))
      (node (ref "U$9") (pin "P$2") (pinfunction "VREFA_P$2") (pintype "power_in"))
    )
    (net (code "205") (name "unconnected-(FT230X-CBUS0-Pad12)") (class "Default")
      (node (ref "FT230X") (pin "12") (pinfunction "CBUS0_12") (pintype "bidirectional"))
    )
    (net (code "206") (name "unconnected-(FT230X-CBUS1-Pad11)") (class "Default")
      (node (ref "FT230X") (pin "11") (pinfunction "CBUS1_11") (pintype "bidirectional"))
    )
    (net (code "207") (name "unconnected-(FT230X-CBUS2-Pad5)") (class "Default")
      (node (ref "FT230X") (pin "5") (pinfunction "CBUS2_5") (pintype "bidirectional"))
    )
    (net (code "208") (name "unconnected-(FT230X-CBUS3-Pad14)") (class "Default")
      (node (ref "FT230X") (pin "14") (pinfunction "CBUS3_14") (pintype "bidirectional"))
    )
    (net (code "209") (name "unconnected-(FT230X-CTS#-Pad4)") (class "Default")
      (node (ref "FT230X") (pin "4") (pinfunction "CTS#_4") (pintype "bidirectional"))
    )
    (net (code "210") (name "unconnected-(FT230X-RTS#-Pad16)") (class "Default")
      (node (ref "FT230X") (pin "16") (pinfunction "RTS#_16") (pintype "bidirectional"))
    )
    (net (code "211") (name "unconnected-(IC1-NC-Pad13)") (class "Default")
      (node (ref "IC1") (pin "13") (pinfunction "NC_13") (pintype "bidirectional"))
    )
    (net (code "212") (name "unconnected-(IC1-P0[4]{slash}I2SRX_CLK{slash}RD2{slash}CAP2[0]-Pad81)") (class "Default")
      (node (ref "IC1") (pin "81") (pinfunction "P0[4]/I2SRX_CLK/RD2/CAP2[0]_81") (pintype "bidirectional"))
    )
    (net (code "213") (name "unconnected-(IC1-P0[5]{slash}I2SRX_WS{slash}TD2{slash}CAP2[1]-Pad80)") (class "Default")
      (node (ref "IC1") (pin "80") (pinfunction "P0[5]/I2SRX_WS/TD2/CAP2[1]_80") (pintype "bidirectional"))
    )
    (net (code "214") (name "unconnected-(IC1-P0[21]{slash}RI1{slash}RD1-Pad57)") (class "Default")
      (node (ref "IC1") (pin "57") (pinfunction "P0[21]/RI1/RD1_57") (pintype "bidirectional"))
    )
    (net (code "215") (name "unconnected-(IC1-P0[22]{slash}RTS1{slash}TD1-Pad56)") (class "Default")
      (node (ref "IC1") (pin "56") (pinfunction "P0[22]/RTS1/TD1_56") (pintype "bidirectional"))
    )
    (net (code "216") (name "unconnected-(IC1-P0[27]{slash}SDA0{slash}USB_SDA-Pad25)") (class "Default")
      (node (ref "IC1") (pin "25") (pinfunction "P0[27]/SDA0/USB_SDA_25") (pintype "bidirectional"))
    )
    (net (code "217") (name "unconnected-(IC1-P0[28]{slash}SCL0{slash}USB_SCL-Pad24)") (class "Default")
      (node (ref "IC1") (pin "24") (pinfunction "P0[28]/SCL0/USB_SCL_24") (pintype "bidirectional"))
    )
    (net (code "218") (name "unconnected-(IC1-P0[29]{slash}USB_DPLUS-Pad29)") (class "Default")
      (node (ref "IC1") (pin "29") (pinfunction "P0[29]/USB_DPLUS_29") (pintype "bidirectional"))
    )
    (net (code "219") (name "unconnected-(IC1-P0[30]{slash}USB_DMINUS-Pad30)") (class "Default")
      (node (ref "IC1") (pin "30") (pinfunction "P0[30]/USB_DMINUS_30") (pintype "bidirectional"))
    )
    (net (code "220") (name "unconnected-(IC1-P1[10]{slash}ENET_RXD1-Pad90)") (class "Default")
      (node (ref "IC1") (pin "90") (pinfunction "P1[10]/ENET_RXD1_90") (pintype "bidirectional"))
    )
    (net (code "221") (name "unconnected-(IC1-P1[14]{slash}ENET_RX_ER-Pad89)") (class "Default")
      (node (ref "IC1") (pin "89") (pinfunction "P1[14]/ENET_RX_ER_89") (pintype "bidirectional"))
    )
    (net (code "222") (name "unconnected-(IC1-P1[15]{slash}ENET_REF_CLK-Pad88)") (class "Default")
      (node (ref "IC1") (pin "88") (pinfunction "P1[15]/ENET_REF_CLK_88") (pintype "bidirectional"))
    )
    (net (code "223") (name "unconnected-(IC1-P1[24]{slash}MCI2{slash}PWM1[5]{slash}MOSI0-Pad38)") (class "Default")
      (node (ref "IC1") (pin "38") (pinfunction "P1[24]/MCI2/PWM1[5]/MOSI0_38") (pintype "bidirectional"))
    )
    (net (code "224") (name "unconnected-(IC1-P1[25]{slash}MCOA1{slash}MAT1[1]-Pad39)") (class "Default")
      (node (ref "IC1") (pin "39") (pinfunction "P1[25]/MCOA1/MAT1[1]_39") (pintype "bidirectional"))
    )
    (net (code "225") (name "unconnected-(IC1-P1[26]{slash}MCOB1{slash}PWM1[6]{slash}CAP0[0]-Pad40)") (class "Default")
      (node (ref "IC1") (pin "40") (pinfunction "P1[26]/MCOB1/PWM1[6]/CAP0[0]_40") (pintype "bidirectional"))
    )
    (net (code "226") (name "unconnected-(IC1-P1[28]{slash}MCOA2{slash}PCAP1[0]{slash}MAT0[0]-Pad44)") (class "Default")
      (node (ref "IC1") (pin "44") (pinfunction "P1[28]/MCOA2/PCAP1[0]/MAT0[0]_44") (pintype "bidirectional"))
    )
    (net (code "227") (name "unconnected-(IC1-P1[29]{slash}MCOB2{slash}PCAP1[1]{slash}MAT0[1]-Pad45)") (class "Default")
      (node (ref "IC1") (pin "45") (pinfunction "P1[29]/MCOB2/PCAP1[1]/MAT0[1]_45") (pintype "bidirectional"))
    )
    (net (code "228") (name "unconnected-(IC1-P1[30]{slash}VBUS{slash}AD0[4]-Pad21)") (class "Default")
      (node (ref "IC1") (pin "21") (pinfunction "P1[30]/VBUS/AD0[4]_21") (pintype "bidirectional"))
    )
    (net (code "229") (name "unconnected-(IC1-P1[31]{slash}SCK1{slash}AD0[5]-Pad20)") (class "Default")
      (node (ref "IC1") (pin "20") (pinfunction "P1[31]/SCK1/AD0[5]_20") (pintype "bidirectional"))
    )
    (net (code "230") (name "unconnected-(IC1-P2[8]{slash}TD2{slash}TXD2{slash}ENET_MDC-Pad65)") (class "Default")
      (node (ref "IC1") (pin "65") (pinfunction "P2[8]/TD2/TXD2/ENET_MDC_65") (pintype "bidirectional"))
    )
    (net (code "231") (name "unconnected-(IC1-P2[9]{slash}USB_CONNECT{slash}RXD2{slash}ENET_MDIO-Pad64)") (class "Default")
      (node (ref "IC1") (pin "64") (pinfunction "P2[9]/USB_CONNECT/RXD2/ENET_MDIO_64") (pintype "bidirectional"))
    )
    (net (code "232") (name "unconnected-(IC1-P2[13]{slash}EINT3{slash}I2STX_SDA-Pad50)") (class "Default")
      (node (ref "IC1") (pin "50") (pinfunction "P2[13]/EINT3/I2STX_SDA_50") (pintype "bidirectional"))
    )
    (net (code "233") (name "unconnected-(IC1-P3[25]{slash}MAT0[0]{slash}PWM1[2]-Pad27)") (class "Default")
      (node (ref "IC1") (pin "27") (pinfunction "P3[25]/MAT0[0]/PWM1[2]_27") (pintype "bidirectional"))
    )
    (net (code "234") (name "unconnected-(IC1-P3[26]{slash}STCLK{slash}MAT0[1]{slash}PWM1[3]-Pad26)") (class "Default")
      (node (ref "IC1") (pin "26") (pinfunction "P3[26]/STCLK/MAT0[1]/PWM1[3]_26") (pintype "bidirectional"))
    )
    (net (code "235") (name "unconnected-(IC1-P4[28]{slash}RX_MCLK{slash}MAT2[0]{slash}TXD3-Pad82)") (class "Default")
      (node (ref "IC1") (pin "82") (pinfunction "P4[28]/RX_MCLK/MAT2[0]/TXD3_82") (pintype "bidirectional"))
    )
    (net (code "236") (name "unconnected-(IC1-P4[29]{slash}TX_MCLK{slash}MAT2[1]{slash}RXD3-Pad85)") (class "Default")
      (node (ref "IC1") (pin "85") (pinfunction "P4[29]/TX_MCLK/MAT2[1]/RXD3_85") (pintype "bidirectional"))
    )
    (net (code "237") (name "unconnected-(IC1-RSTOUT-Pad14)") (class "Default")
      (node (ref "IC1") (pin "14") (pinfunction "RSTOUT_14") (pintype "bidirectional"))
    )
    (net (code "238") (name "unconnected-(IC1-RTCX1-Pad16)") (class "Default")
      (node (ref "IC1") (pin "16") (pinfunction "RTCX1_16") (pintype "bidirectional"))
    )
    (net (code "239") (name "unconnected-(IC1-RTCX2-Pad18)") (class "Default")
      (node (ref "IC1") (pin "18") (pinfunction "RTCX2_18") (pintype "bidirectional"))
    )
    (net (code "240") (name "unconnected-(IC2-N{slash}C-Pad53)") (class "Default")
      (node (ref "IC2") (pin "53") (pinfunction "N/C_53") (pintype "no_connect"))
    )
    (net (code "241") (name "unconnected-(JTAG_A3PN-Pad4)") (class "Default")
      (node (ref "JTAG_A3PN") (pin "4") (pinfunction "4_4") (pintype "passive"))
    )
    (net (code "242") (name "unconnected-(JTAG_LPC-Pad19)") (class "Default")
      (node (ref "JTAG_LPC") (pin "19") (pinfunction "19_19") (pintype "passive"))
    )
    (net (code "243") (name "~{RES}") (class "Default")
      (node (ref "IC1") (pin "17") (pinfunction "RESET_17") (pintype "bidirectional"))
      (node (ref "JTAG_LPC") (pin "15") (pinfunction "15_15") (pintype "passive"))
      (node (ref "R8") (pin "1") (pinfunction "1_1") (pintype "passive"))
      (node (ref "RESET") (pin "P$2") (pinfunction "1_P$2") (pintype "passive"))
    )
  )
)
